# Charger_Control_Board_rev7.net
KiCad netlist of a schematic drawn in EAGLE
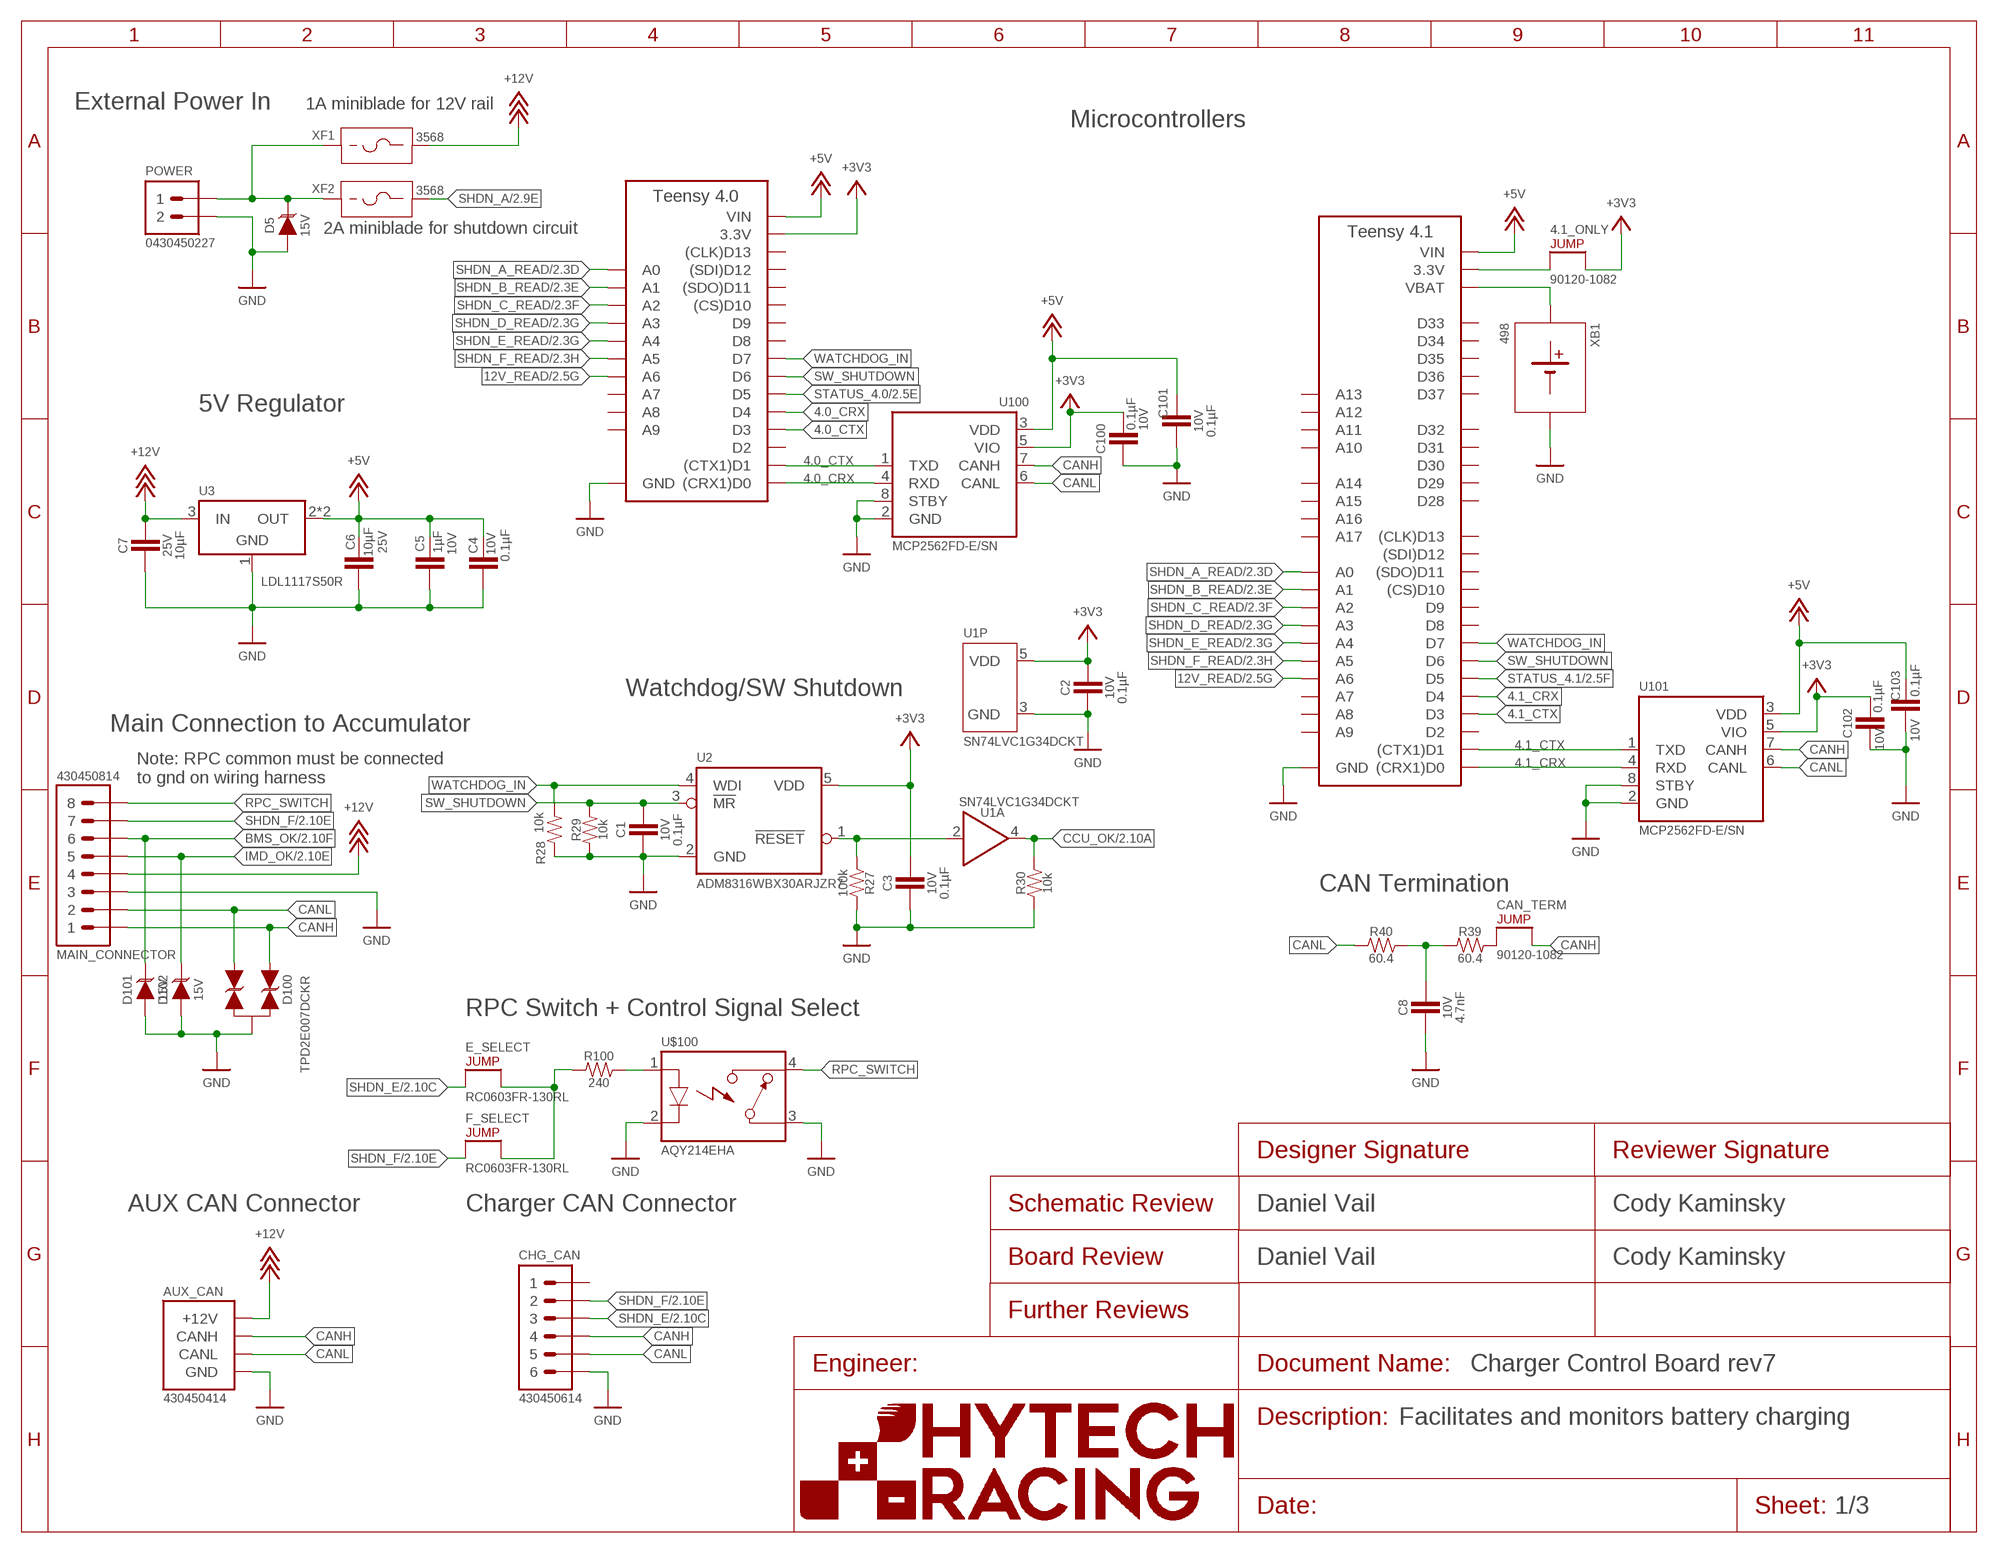
[diagram p0: schematic, sheet 1]
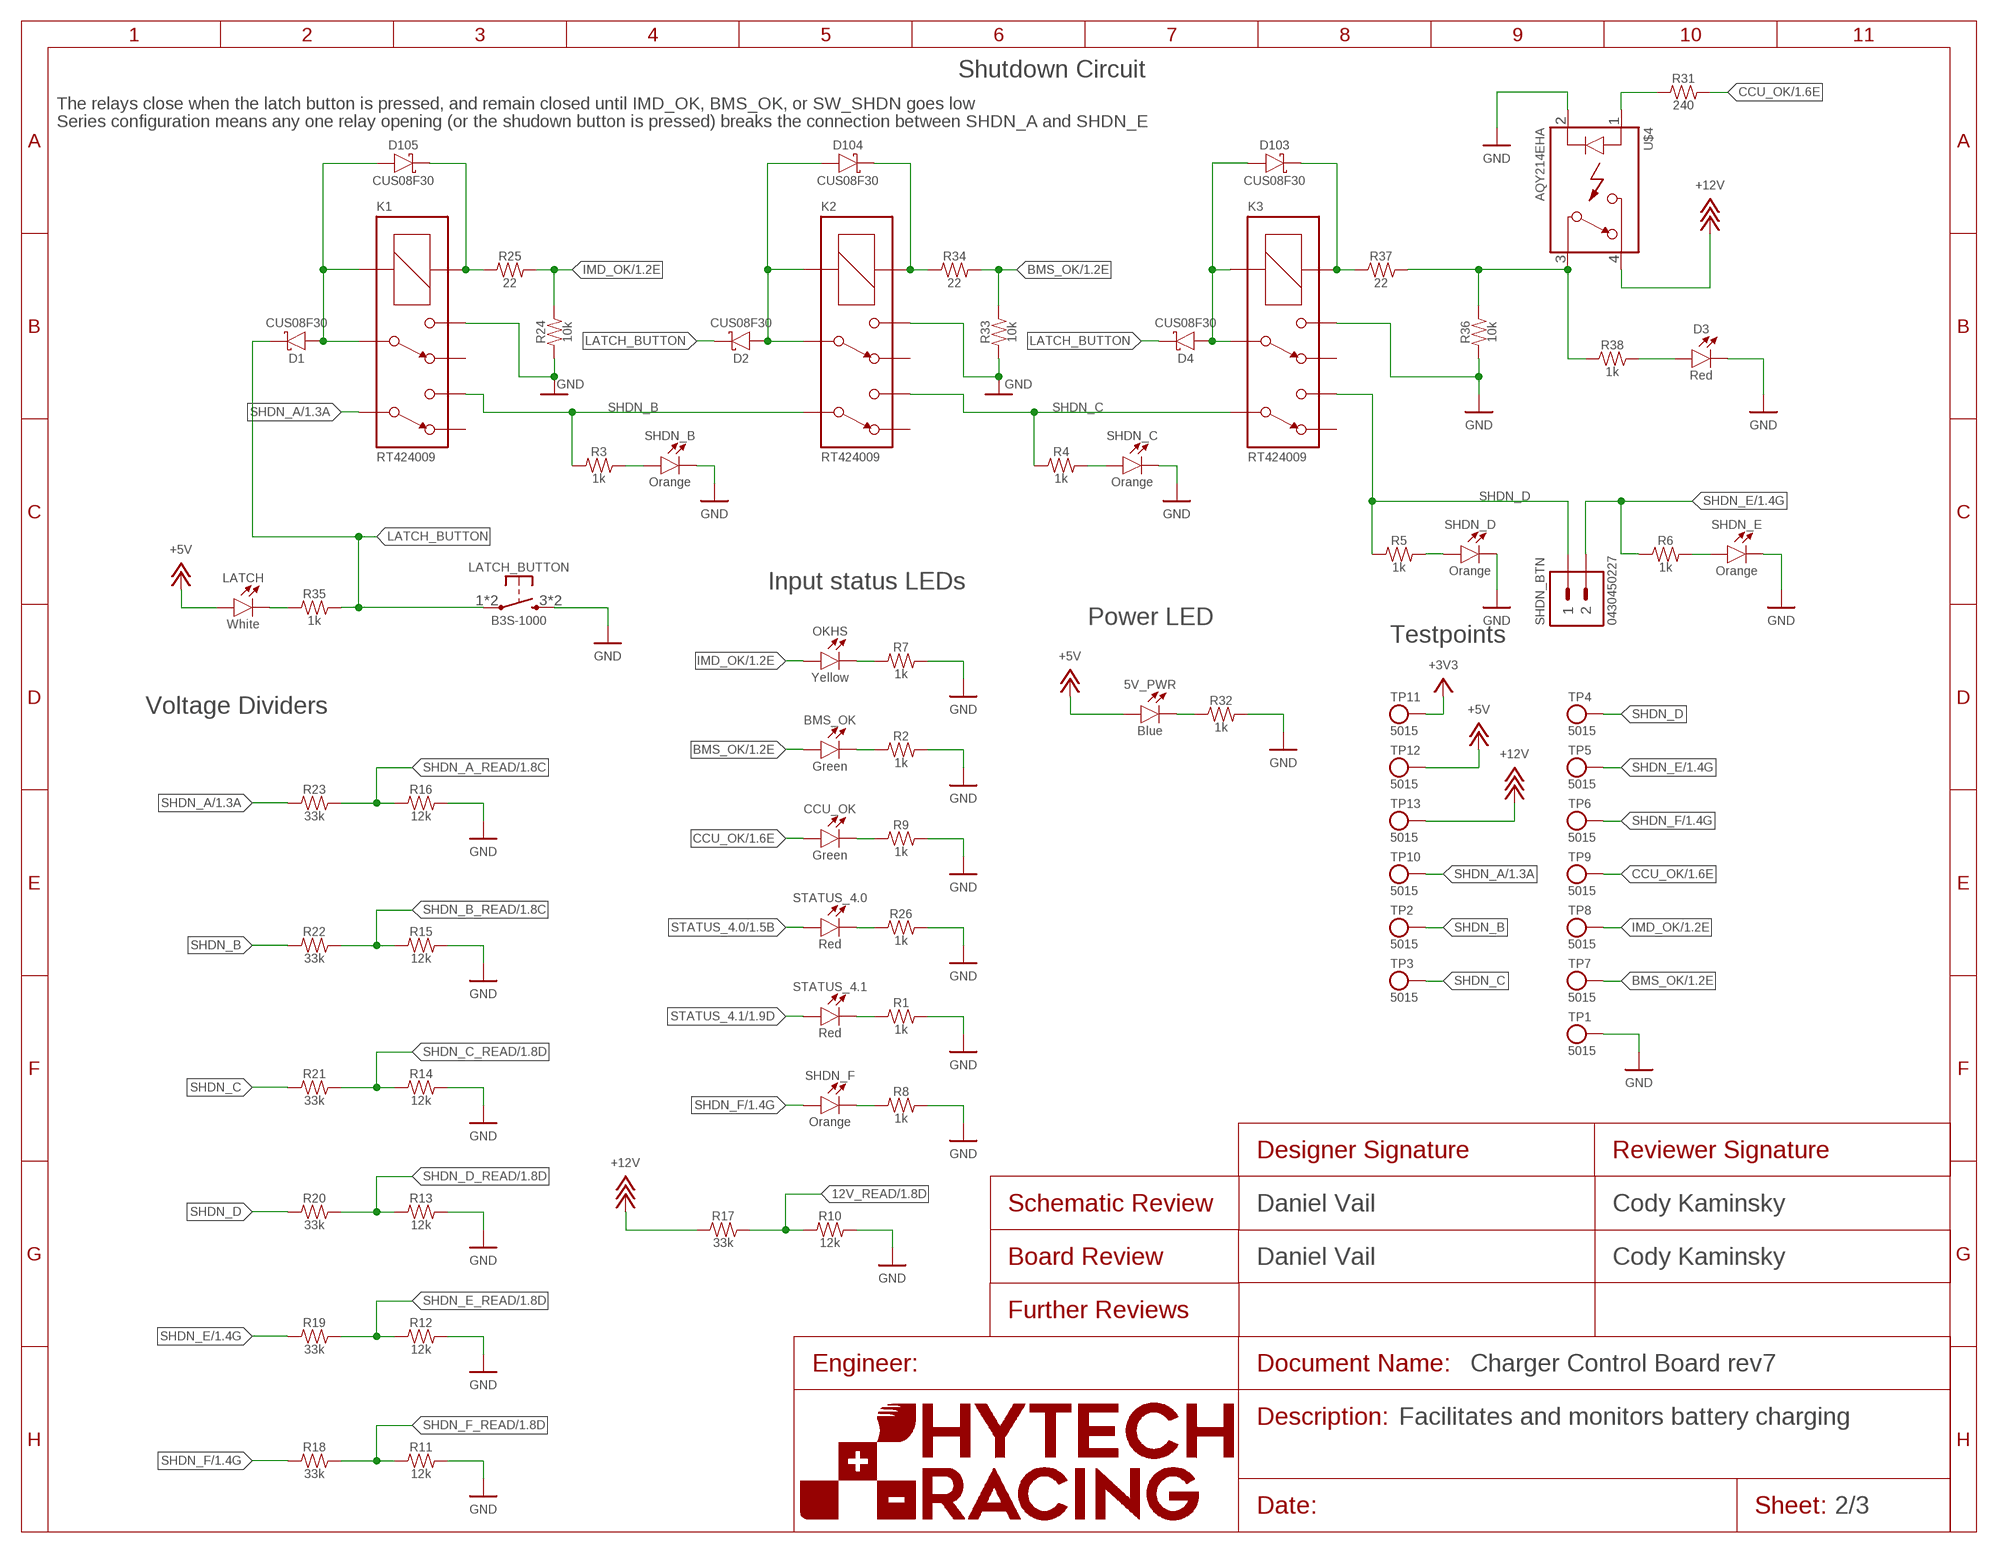
[diagram p1: schematic, sheet 2]
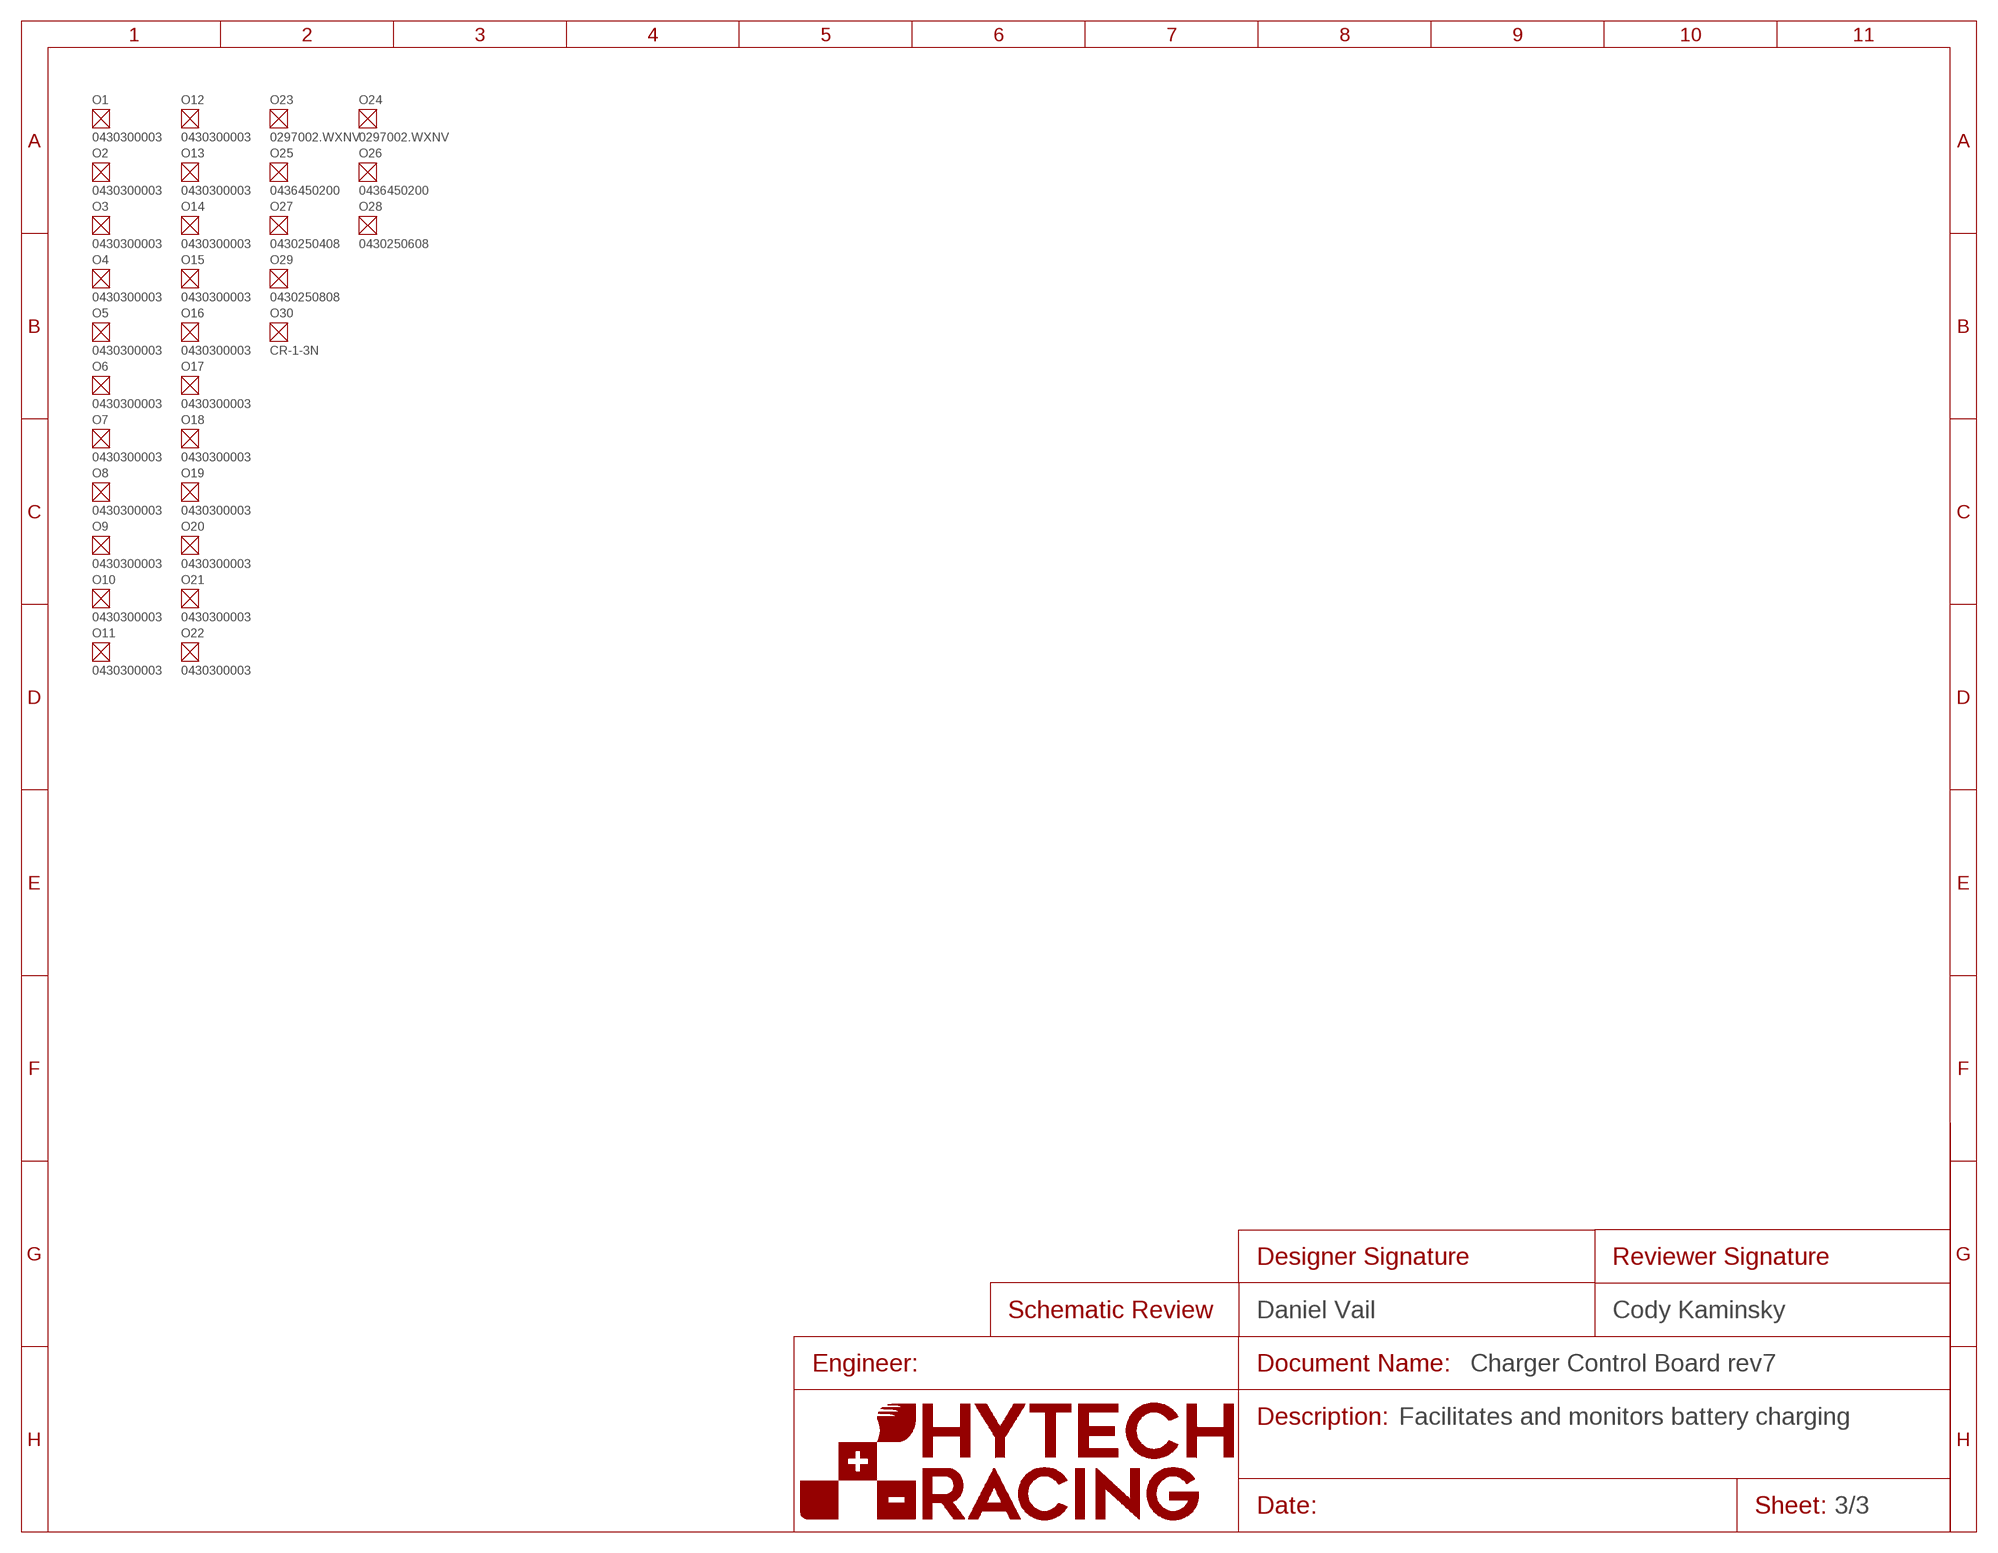
[diagram p2: schematic, sheet 3]

(export (version "E")
  (design (tool "Eeschema 10.0.6"))
  (components
    (comp (ref "4.1_ONLY")
      (value "JUMPER__1X02")
      (footprint "eagle-import:1X02")
      (fields (field (name "MANUFACTURER") "Molex") (field (name "MPN") "90120-1082 "))
      (libsource (lib "eagle-import") (part "JUMPER_?_1X02"))
    )
    (comp (ref "A1")
      (value "TEENSY_4.1")
      (footprint "eagle-import:TEENSY_LONG_EXT")
      (libsource (lib "eagle-import") (part "TEENSY_4.1"))
    )
    (comp (ref "A2")
      (value "TEENSY_4.0")
      (footprint "eagle-import:TEENSY_SHORT")
      (libsource (lib "eagle-import") (part "TEENSY_4.0"))
    )
    (comp (ref "AUX_CAN")
      (value "CONNECTOR-CAN_MF_T_V_")
      (footprint "eagle-import:MOLEX_MICROFIT_PTH_VERTICAL_04_DUAL")
      (fields (field (name "MPN") "430450414") (field (name "MANUFACTURER") "Molex"))
      (libsource (lib "eagle-import") (part "CONNECTOR-CAN_?_MF_T_V"))
    )
    (comp (ref "C1")
      (value "CAPACITOR_0603_10V_0.1UF")
      (footprint "eagle-import:0603-CAP")
      (fields
        (field (name "CAPACITANCE") "0.1µF")
        (field (name "MANUFACTURER") "Vishay Vitramon")
        (field (name "MPN") "VJ0603Y104JXQPW1BC")
        (field (name "TOLERANCE") "5%")
        (field (name "VOLTAGE") "10V")
      )
      (libsource (lib "eagle-import") (part "CAPACITOR_?_060310V_0.1UF"))
    )
    (comp (ref "C2")
      (value "CAPACITOR_0603_10V_0.1UF")
      (footprint "eagle-import:0603-CAP")
      (fields
        (field (name "CAPACITANCE") "0.1µF")
        (field (name "MANUFACTURER") "Vishay Vitramon")
        (field (name "MPN") "VJ0603Y104JXQPW1BC")
        (field (name "TOLERANCE") "5%")
        (field (name "VOLTAGE") "10V")
      )
      (libsource (lib "eagle-import") (part "CAPACITOR_?_060310V_0.1UF"))
    )
    (comp (ref "C3")
      (value "CAPACITOR_0603_10V_0.1UF")
      (footprint "eagle-import:0603-CAP")
      (fields
        (field (name "CAPACITANCE") "0.1µF")
        (field (name "MANUFACTURER") "Vishay Vitramon")
        (field (name "MPN") "VJ0603Y104JXQPW1BC")
        (field (name "TOLERANCE") "5%")
        (field (name "VOLTAGE") "10V")
      )
      (libsource (lib "eagle-import") (part "CAPACITOR_?_060310V_0.1UF"))
    )
    (comp (ref "C4")
      (value "CAPACITOR_0603_10V_0.1UF")
      (footprint "eagle-import:0603-CAP")
      (fields
        (field (name "CAPACITANCE") "0.1µF")
        (field (name "MANUFACTURER") "Vishay Vitramon")
        (field (name "MPN") "VJ0603Y104JXQPW1BC")
        (field (name "TOLERANCE") "5%")
        (field (name "VOLTAGE") "10V")
      )
      (libsource (lib "eagle-import") (part "CAPACITOR_?_060310V_0.1UF"))
    )
    (comp (ref "C5")
      (value "CAPACITOR_0603_10V_1UF")
      (footprint "eagle-import:0603-CAP")
      (fields
        (field (name "CAPACITANCE") "1µF")
        (field (name "MANUFACTURER") "Yageo")
        (field (name "MPN") "CC0603KRX7R6BB105")
        (field (name "TOLERANCE") "10%")
        (field (name "VOLTAGE") "10V")
      )
      (libsource (lib "eagle-import") (part "CAPACITOR_?_060310V_1UF"))
    )
    (comp (ref "C6")
      (value "CAPACITOR_0603_25V_10UF")
      (footprint "eagle-import:0603-CAP")
      (fields
        (field (name "CAPACITANCE") "10µF")
        (field (name "MANUFACTURER") "Murata Electronics")
        (field (name "MPN") "GRM188R61E106MA73D")
        (field (name "TOLERANCE") "20%")
        (field (name "VOLTAGE") "25V")
      )
      (libsource (lib "eagle-import") (part "CAPACITOR_?_060325V_10UF"))
    )
    (comp (ref "C7")
      (value "CAPACITOR_0603_25V_10UF")
      (footprint "eagle-import:0603-CAP")
      (fields
        (field (name "CAPACITANCE") "10µF")
        (field (name "MANUFACTURER") "Murata Electronics")
        (field (name "MPN") "GRM188R61E106MA73D")
        (field (name "TOLERANCE") "20%")
        (field (name "VOLTAGE") "25V")
      )
      (libsource (lib "eagle-import") (part "CAPACITOR_?_060325V_10UF"))
    )
    (comp (ref "C8")
      (value "CAPACITOR_0603_10V_4.7NF")
      (footprint "eagle-import:0603-CAP")
      (fields
        (field (name "CAPACITANCE") "4.7nF")
        (field (name "MANUFACTURER") "Würth Elektronik")
        (field (name "MPN") "885012206012")
        (field (name "TOLERANCE") "10%")
        (field (name "VOLTAGE") "10V")
      )
      (libsource (lib "eagle-import") (part "CAPACITOR_?_060310V_4.7NF"))
    )
    (comp (ref "C100")
      (value "CAPACITOR_0603_10V_0.1UF")
      (footprint "eagle-import:0603-CAP")
      (fields
        (field (name "CAPACITANCE") "0.1µF")
        (field (name "MANUFACTURER") "Vishay Vitramon")
        (field (name "MPN") "VJ0603Y104JXQPW1BC")
        (field (name "TOLERANCE") "5%")
        (field (name "VOLTAGE") "10V")
      )
      (libsource (lib "eagle-import") (part "CAPACITOR_?_060310V_0.1UF"))
    )
    (comp (ref "C101")
      (value "CAPACITOR_0603_10V_0.1UF")
      (footprint "eagle-import:0603-CAP")
      (fields
        (field (name "CAPACITANCE") "0.1µF")
        (field (name "MANUFACTURER") "Vishay Vitramon")
        (field (name "MPN") "VJ0603Y104JXQPW1BC")
        (field (name "TOLERANCE") "5%")
        (field (name "VOLTAGE") "10V")
      )
      (libsource (lib "eagle-import") (part "CAPACITOR_?_060310V_0.1UF"))
    )
    (comp (ref "C102")
      (value "CAPACITOR_0603_10V_0.1UF")
      (footprint "eagle-import:0603-CAP")
      (fields
        (field (name "CAPACITANCE") "0.1µF")
        (field (name "MANUFACTURER") "Vishay Vitramon")
        (field (name "MPN") "VJ0603Y104JXQPW1BC")
        (field (name "TOLERANCE") "5%")
        (field (name "VOLTAGE") "10V")
      )
      (libsource (lib "eagle-import") (part "CAPACITOR_?_060310V_0.1UF"))
    )
    (comp (ref "C103")
      (value "CAPACITOR_0603_10V_0.1UF")
      (footprint "eagle-import:0603-CAP")
      (fields
        (field (name "CAPACITANCE") "0.1µF")
        (field (name "MANUFACTURER") "Vishay Vitramon")
        (field (name "MPN") "VJ0603Y104JXQPW1BC")
        (field (name "TOLERANCE") "5%")
        (field (name "VOLTAGE") "10V")
      )
      (libsource (lib "eagle-import") (part "CAPACITOR_?_060310V_0.1UF"))
    )
    (comp (ref "CAN_TERM")
      (value "JUMPER__1X02")
      (footprint "eagle-import:1X02")
      (fields (field (name "MANUFACTURER") "Molex") (field (name "MPN") "90120-1082 "))
      (libsource (lib "eagle-import") (part "JUMPER_?_1X02"))
    )
    (comp (ref "CHG_CAN")
      (value "CONNECTOR-6_MF_T_V_")
      (footprint "eagle-import:MOLEX_MICROFIT_PTH_VERTICAL_06_DUAL")
      (fields (field (name "MPN") "430450614") (field (name "MANUFACTURER") "MOLEX"))
      (libsource (lib "eagle-import") (part "CONNECTOR-6_?_MF_T_V"))
    )
    (comp (ref "D5")
      (value "TVS_15V")
      (footprint "eagle-import:SOT-23")
      (fields
        (field (name "MANUFACTURER") "Vishay General Semiconductor - Diodes Division")
        (field (name "MPN") "GSOT15-E3-08")
        (field (name "VOLTAGE") "15V")
      )
      (libsource (lib "eagle-import") (part "TVS_15V"))
    )
    (comp (ref "D100")
      (value "TVS_BIDIRECTIONAL_DUAL")
      (footprint "eagle-import:SC-70-3")
      (fields (field (name "MPN") "TPD2E007DCKR") (field (name "MANUFACTURER") "Texas Instruments"))
      (libsource (lib "eagle-import") (part "TVS_BIDIRECTIONAL_DUAL"))
    )
    (comp (ref "D101")
      (value "TVS_15V")
      (footprint "eagle-import:SOT-23")
      (fields
        (field (name "MANUFACTURER") "Vishay General Semiconductor - Diodes Division")
        (field (name "MPN") "GSOT15-E3-08")
        (field (name "VOLTAGE") "15V")
      )
      (libsource (lib "eagle-import") (part "TVS_15V"))
    )
    (comp (ref "D102")
      (value "TVS_15V")
      (footprint "eagle-import:SOT-23")
      (fields
        (field (name "MANUFACTURER") "Vishay General Semiconductor - Diodes Division")
        (field (name "MPN") "GSOT15-E3-08")
        (field (name "VOLTAGE") "15V")
      )
      (libsource (lib "eagle-import") (part "TVS_15V"))
    )
    (comp (ref "E_SELECT")
      (value "JUMPER_0603_")
      (footprint "eagle-import:0603-RES")
      (fields (field (name "MPN") "RC0603FR-130RL") (field (name "MANUFACTURER") "YAGEO"))
      (libsource (lib "eagle-import") (part "JUMPER_?_0603"))
    )
    (comp (ref "F_SELECT")
      (value "JUMPER_0603_")
      (footprint "eagle-import:0603-RES")
      (fields (field (name "MPN") "RC0603FR-130RL") (field (name "MANUFACTURER") "YAGEO"))
      (libsource (lib "eagle-import") (part "JUMPER_?_0603"))
    )
    (comp (ref "MAIN_CONNECTOR")
      (value "CONNECTOR-8_MF_T_V_")
      (footprint "eagle-import:MOLEX_MICROFIT_PTH_VERTICAL_08_DUAL")
      (fields (field (name "MPN") "430450814") (field (name "MANUFACTURER") "MOLEX"))
      (libsource (lib "eagle-import") (part "CONNECTOR-8_?_MF_T_V"))
    )
    (comp (ref "POWER")
      (value "CONNECTOR-2_μF_T_V_")
      (footprint "eagle-import:MOLEX_MICROFIT_PTH_VERTICAL_02_DUAL")
      (fields (field (name "MPN") "0430450227") (field (name "MANUFACTURER") "Molex"))
      (libsource (lib "eagle-import") (part "CONNECTOR-2_?_μF_T_V"))
    )
    (comp (ref "R27")
      (value "RESISTOR_0603_100K")
      (footprint "eagle-import:0603-RES")
      (fields
        (field (name "MANUFACTURER") "Yageo")
        (field (name "MPN") "RC0603FR-07100KL")
        (field (name "POWER") "0.1W")
        (field (name "RESISTANCE") "100k")
      )
      (libsource (lib "eagle-import") (part "RESISTOR_?_0603100K"))
    )
    (comp (ref "R28")
      (value "RESISTOR_0603_10K")
      (footprint "eagle-import:0603-RES")
      (fields
        (field (name "MANUFACTURER") "Yageo")
        (field (name "MPN") "RC0603FR-0710KL")
        (field (name "POWER") "0.1W")
        (field (name "RESISTANCE") "10k")
      )
      (libsource (lib "eagle-import") (part "RESISTOR_?_060310K"))
    )
    (comp (ref "R29")
      (value "RESISTOR_0603_10K")
      (footprint "eagle-import:0603-RES")
      (fields
        (field (name "MANUFACTURER") "Yageo")
        (field (name "MPN") "RC0603FR-0710KL")
        (field (name "POWER") "0.1W")
        (field (name "RESISTANCE") "10k")
      )
      (libsource (lib "eagle-import") (part "RESISTOR_?_060310K"))
    )
    (comp (ref "R30")
      (value "RESISTOR_0603_10K")
      (footprint "eagle-import:0603-RES")
      (fields
        (field (name "MANUFACTURER") "Yageo")
        (field (name "MPN") "RC0603FR-0710KL")
        (field (name "POWER") "0.1W")
        (field (name "RESISTANCE") "10k")
      )
      (libsource (lib "eagle-import") (part "RESISTOR_?_060310K"))
    )
    (comp (ref "R39")
      (value "RESISTOR_0603_60.4")
      (footprint "eagle-import:0603-RES")
      (fields
        (field (name "MANUFACTURER") "Yageo")
        (field (name "MPN") "RC0603FR-0760R4L")
        (field (name "POWER") "0.1W")
        (field (name "RESISTANCE") "60.4")
      )
      (libsource (lib "eagle-import") (part "RESISTOR_?_060360.4"))
    )
    (comp (ref "R40")
      (value "RESISTOR_0603_60.4")
      (footprint "eagle-import:0603-RES")
      (fields
        (field (name "MANUFACTURER") "Yageo")
        (field (name "MPN") "RC0603FR-0760R4L")
        (field (name "POWER") "0.1W")
        (field (name "RESISTANCE") "60.4")
      )
      (libsource (lib "eagle-import") (part "RESISTOR_?_060360.4"))
    )
    (comp (ref "R100")
      (value "RESISTOR_0603_240")
      (footprint "eagle-import:0603-RES")
      (fields
        (field (name "MANUFACTURER") "Yageo")
        (field (name "MPN") "RC0603FR-07240RL")
        (field (name "POWER") "0.1W")
        (field (name "RESISTANCE") "240")
      )
      (libsource (lib "eagle-import") (part "HyTechDevices_Jumper_RESISTOR_?_0603240"))
    )
    (comp (ref "U$100")
      (value "RELAY_SOLIDSTATE_NO")
      (footprint "eagle-import:DIP-4")
      (fields (field (name "MPN") "AQY214EHA") (field (name "MANUFACTURER") "AQY214EHA"))
      (libsource (lib "eagle-import") (part "RELAY_SOLIDSTATE_NO"))
    )
    (comp (ref "U1")
      (value "LOGICGATE_BUFFER")
      (footprint "eagle-import:SC-70-5")
      (fields (field (name "MANUFACTURER") "Texas Instruments"))
      (libsource (lib "eagle-import") (part "LOGICGATE_BUFFER"))
    )
    (comp (ref "U2")
      (value "ADM8316WBX30")
      (footprint "eagle-import:SOT-23-5")
      (fields (field (name "MANUFACTURER") "Analog Devices Inc.") (field (name "MPN") "ADM8316WBX30ARJZR7"))
      (libsource (lib "eagle-import") (part "ADM8316WBX30"))
    )
    (comp (ref "U3")
      (value "VOLTAGE_REGULATOR_SOT-223_5V")
      (footprint "eagle-import:SOT-223")
      (fields (field (name "MANUFACTURER") "STMicroelectronics") (field (name "MPN") "LDL1117S50R"))
      (libsource (lib "eagle-import") (part "VOLTAGE_REGULATOR_?_SOT-2235V"))
    )
    (comp (ref "U100")
      (value "MCP2562FD")
      (footprint "eagle-import:SOIC-08(NARROW,0.15_)")
      (fields (field (name "MPN") "MCP2562FD-E/SN") (field (name "MANUFACTURER") "Microchip Technology"))
      (libsource (lib "eagle-import") (part "MCP2562FD"))
    )
    (comp (ref "U101")
      (value "MCP2562FD")
      (footprint "eagle-import:SOIC-08(NARROW,0.15_)")
      (fields (field (name "MPN") "MCP2562FD-E/SN") (field (name "MANUFACTURER") "Microchip Technology"))
      (libsource (lib "eagle-import") (part "MCP2562FD"))
    )
    (comp (ref "XB1")
      (value "BATTERY_HOLDER_KEYSTONE_498")
      (footprint "eagle-import:498")
      (fields (field (name "MPN") "498") (field (name "MANUFACTURER") "Keystone Electronics"))
      (libsource (lib "eagle-import") (part "BATTERY_HOLDER_KEYSTONE_498"))
    )
    (comp (ref "XF1")
      (value "FUSE_HOLDER_MINIBLADEPTH")
      (footprint "eagle-import:3568")
      (fields (field (name "MANUFACTURER") "Keystone") (field (name "MPN") "3568"))
      (libsource (lib "eagle-import") (part "FUSE_HOLDER_PTHMINIBLADE"))
    )
    (comp (ref "XF2")
      (value "FUSE_HOLDER_MINIBLADEPTH")
      (footprint "eagle-import:3568")
      (fields (field (name "MANUFACTURER") "Keystone") (field (name "MPN") "3568"))
      (libsource (lib "eagle-import") (part "FUSE_HOLDER_PTHMINIBLADE"))
    )
    (comp (ref "5V_PWR")
      (value "LED_0603_BLUE")
      (footprint "eagle-import:0603-LED")
      (fields
        (field (name "COLOR") "Blue")
        (field (name "MANUFACTURER") "Kingbright")
        (field (name "MPN") "APT1608VBC/D")
      )
      (libsource (lib "eagle-import") (part "LED_?_0603BLUE"))
    )
    (comp (ref "BMS_OK")
      (value "LED_0603_GREEN")
      (footprint "eagle-import:0603-LED")
      (fields
        (field (name "COLOR") "Green")
        (field (name "MANUFACTURER") "Kingbright")
        (field (name "MPN") "APT1608ZGCK")
      )
      (libsource (lib "eagle-import") (part "LED_?_0603GREEN"))
    )
    (comp (ref "CCU_OK")
      (value "LED_0603_GREEN")
      (footprint "eagle-import:0603-LED")
      (fields
        (field (name "COLOR") "Green")
        (field (name "MANUFACTURER") "Kingbright")
        (field (name "MPN") "APT1608ZGCK")
      )
      (libsource (lib "eagle-import") (part "LED_?_0603GREEN"))
    )
    (comp (ref "D1")
      (value "SCHOTTKY_SOD323_30V")
      (footprint "eagle-import:SOD-323")
      (fields
        (field (name "MANUFACTURER") "Toshiba Semiconductor and Storage")
        (field (name "MPN") "CUS08F30")
        (field (name "VOLTAGE") "30V")
      )
      (libsource (lib "eagle-import") (part "SCHOTTKY_?_SOD32330V"))
    )
    (comp (ref "D2")
      (value "SCHOTTKY_SOD323_30V")
      (footprint "eagle-import:SOD-323")
      (fields
        (field (name "MANUFACTURER") "Toshiba Semiconductor and Storage")
        (field (name "MPN") "CUS08F30")
        (field (name "VOLTAGE") "30V")
      )
      (libsource (lib "eagle-import") (part "SCHOTTKY_?_SOD32330V"))
    )
    (comp (ref "D3")
      (value "LED_0603_RED")
      (footprint "eagle-import:0603-LED")
      (fields
        (field (name "COLOR") "Red")
        (field (name "MANUFACTURER") "Kingbright")
        (field (name "MPN") "APT1608SECK/J3-PRV")
      )
      (libsource (lib "eagle-import") (part "LED_?_0603RED"))
    )
    (comp (ref "D4")
      (value "SCHOTTKY_SOD323_30V")
      (footprint "eagle-import:SOD-323")
      (fields
        (field (name "MANUFACTURER") "Toshiba Semiconductor and Storage")
        (field (name "MPN") "CUS08F30")
        (field (name "VOLTAGE") "30V")
      )
      (libsource (lib "eagle-import") (part "SCHOTTKY_?_SOD32330V"))
    )
    (comp (ref "D103")
      (value "SCHOTTKY_SOD323_30V")
      (footprint "eagle-import:SOD-323")
      (fields
        (field (name "MANUFACTURER") "Toshiba Semiconductor and Storage")
        (field (name "MPN") "CUS08F30")
        (field (name "VOLTAGE") "30V")
      )
      (libsource (lib "eagle-import") (part "SCHOTTKY_?_SOD32330V"))
    )
    (comp (ref "D104")
      (value "SCHOTTKY_SOD323_30V")
      (footprint "eagle-import:SOD-323")
      (fields
        (field (name "MANUFACTURER") "Toshiba Semiconductor and Storage")
        (field (name "MPN") "CUS08F30")
        (field (name "VOLTAGE") "30V")
      )
      (libsource (lib "eagle-import") (part "SCHOTTKY_?_SOD32330V"))
    )
    (comp (ref "D105")
      (value "SCHOTTKY_SOD323_30V")
      (footprint "eagle-import:SOD-323")
      (fields
        (field (name "MANUFACTURER") "Toshiba Semiconductor and Storage")
        (field (name "MPN") "CUS08F30")
        (field (name "VOLTAGE") "30V")
      )
      (libsource (lib "eagle-import") (part "SCHOTTKY_?_SOD32330V"))
    )
    (comp (ref "K1")
      (value "RELAY_DPDT")
      (footprint "eagle-import:RT_2_")
      (fields (field (name "MPN") "RT424009") (field (name "MANUFACTURER") "TE Connectivity"))
      (libsource (lib "eagle-import") (part "RELAY_DPDT"))
    )
    (comp (ref "K2")
      (value "RELAY_DPDT")
      (footprint "eagle-import:RT_2_")
      (fields (field (name "MPN") "RT424009") (field (name "MANUFACTURER") "TE Connectivity"))
      (libsource (lib "eagle-import") (part "RELAY_DPDT"))
    )
    (comp (ref "K3")
      (value "RELAY_DPDT")
      (footprint "eagle-import:RT_2_")
      (fields (field (name "MPN") "RT424009") (field (name "MANUFACTURER") "TE Connectivity"))
      (libsource (lib "eagle-import") (part "RELAY_DPDT"))
    )
    (comp (ref "LATCH")
      (value "LED_0603_WHITE")
      (footprint "eagle-import:0603-LED")
      (fields
        (field (name "COLOR") "White")
        (field (name "MANUFACTURER") "Bivar Inc.")
        (field (name "MPN") "SM0603UWC")
      )
      (libsource (lib "eagle-import") (part "LED_?_0603WHITE"))
    )
    (comp (ref "LATCH_BUTTON")
      (value "BUTTON")
      (footprint "eagle-import:B3S-100X")
      (fields (field (name "MPN") "B3S-1000") (field (name "MANUFACTURER") "Omron"))
      (libsource (lib "eagle-import") (part "BUTTON"))
    )
    (comp (ref "OKHS")
      (value "LED_0603_YELLOW")
      (footprint "eagle-import:0603-LED")
      (fields
        (field (name "COLOR") "Yellow")
        (field (name "MANUFACTURER") "Kingbright")
        (field (name "MPN") "APT1608SYCK/J3-PRV")
      )
      (libsource (lib "eagle-import") (part "LED_?_0603YELLOW"))
    )
    (comp (ref "R1")
      (value "RESISTOR_0603_1K")
      (footprint "eagle-import:0603-RES")
      (fields
        (field (name "MANUFACTURER") "Yageo")
        (field (name "MPN") "RC0603FR-071KL")
        (field (name "POWER") "0.1W")
        (field (name "RESISTANCE") "1k")
      )
      (libsource (lib "eagle-import") (part "RESISTOR_?_06031K"))
    )
    (comp (ref "R2")
      (value "RESISTOR_0603_1K")
      (footprint "eagle-import:0603-RES")
      (fields
        (field (name "MANUFACTURER") "Yageo")
        (field (name "MPN") "RC0603FR-071KL")
        (field (name "POWER") "0.1W")
        (field (name "RESISTANCE") "1k")
      )
      (libsource (lib "eagle-import") (part "RESISTOR_?_06031K"))
    )
    (comp (ref "R3")
      (value "RESISTOR_0603_1K")
      (footprint "eagle-import:0603-RES")
      (fields
        (field (name "MANUFACTURER") "Yageo")
        (field (name "MPN") "RC0603FR-071KL")
        (field (name "POWER") "0.1W")
        (field (name "RESISTANCE") "1k")
      )
      (libsource (lib "eagle-import") (part "RESISTOR_?_06031K"))
    )
    (comp (ref "R4")
      (value "RESISTOR_0603_1K")
      (footprint "eagle-import:0603-RES")
      (fields
        (field (name "MANUFACTURER") "Yageo")
        (field (name "MPN") "RC0603FR-071KL")
        (field (name "POWER") "0.1W")
        (field (name "RESISTANCE") "1k")
      )
      (libsource (lib "eagle-import") (part "RESISTOR_?_06031K"))
    )
    (comp (ref "R5")
      (value "RESISTOR_0603_1K")
      (footprint "eagle-import:0603-RES")
      (fields
        (field (name "MANUFACTURER") "Yageo")
        (field (name "MPN") "RC0603FR-071KL")
        (field (name "POWER") "0.1W")
        (field (name "RESISTANCE") "1k")
      )
      (libsource (lib "eagle-import") (part "RESISTOR_?_06031K"))
    )
    (comp (ref "R6")
      (value "RESISTOR_0603_1K")
      (footprint "eagle-import:0603-RES")
      (fields
        (field (name "MANUFACTURER") "Yageo")
        (field (name "MPN") "RC0603FR-071KL")
        (field (name "POWER") "0.1W")
        (field (name "RESISTANCE") "1k")
      )
      (libsource (lib "eagle-import") (part "RESISTOR_?_06031K"))
    )
    (comp (ref "R7")
      (value "RESISTOR_0603_1K")
      (footprint "eagle-import:0603-RES")
      (fields
        (field (name "MANUFACTURER") "Yageo")
        (field (name "MPN") "RC0603FR-071KL")
        (field (name "POWER") "0.1W")
        (field (name "RESISTANCE") "1k")
      )
      (libsource (lib "eagle-import") (part "RESISTOR_?_06031K"))
    )
    (comp (ref "R8")
      (value "RESISTOR_0603_1K")
      (footprint "eagle-import:0603-RES")
      (fields
        (field (name "MANUFACTURER") "Yageo")
        (field (name "MPN") "RC0603FR-071KL")
        (field (name "POWER") "0.1W")
        (field (name "RESISTANCE") "1k")
      )
      (libsource (lib "eagle-import") (part "RESISTOR_?_06031K"))
    )
    (comp (ref "R9")
      (value "RESISTOR_0603_1K")
      (footprint "eagle-import:0603-RES")
      (fields
        (field (name "MANUFACTURER") "Yageo")
        (field (name "MPN") "RC0603FR-071KL")
        (field (name "POWER") "0.1W")
        (field (name "RESISTANCE") "1k")
      )
      (libsource (lib "eagle-import") (part "RESISTOR_?_06031K"))
    )
    (comp (ref "R10")
      (value "RESISTOR_0603_12K")
      (footprint "eagle-import:0603-RES")
      (fields
        (field (name "MANUFACTURER") "Yageo")
        (field (name "MPN") "RC0603FR-0712KL")
        (field (name "POWER") "0.1W")
        (field (name "RESISTANCE") "12k")
      )
      (libsource (lib "eagle-import") (part "RESISTOR_?_060312K"))
    )
    (comp (ref "R11")
      (value "RESISTOR_0603_12K")
      (footprint "eagle-import:0603-RES")
      (fields
        (field (name "MANUFACTURER") "Yageo")
        (field (name "MPN") "RC0603FR-0712KL")
        (field (name "POWER") "0.1W")
        (field (name "RESISTANCE") "12k")
      )
      (libsource (lib "eagle-import") (part "RESISTOR_?_060312K"))
    )
    (comp (ref "R12")
      (value "RESISTOR_0603_12K")
      (footprint "eagle-import:0603-RES")
      (fields
        (field (name "MANUFACTURER") "Yageo")
        (field (name "MPN") "RC0603FR-0712KL")
        (field (name "POWER") "0.1W")
        (field (name "RESISTANCE") "12k")
      )
      (libsource (lib "eagle-import") (part "RESISTOR_?_060312K"))
    )
    (comp (ref "R13")
      (value "RESISTOR_0603_12K")
      (footprint "eagle-import:0603-RES")
      (fields
        (field (name "MANUFACTURER") "Yageo")
        (field (name "MPN") "RC0603FR-0712KL")
        (field (name "POWER") "0.1W")
        (field (name "RESISTANCE") "12k")
      )
      (libsource (lib "eagle-import") (part "RESISTOR_?_060312K"))
    )
    (comp (ref "R14")
      (value "RESISTOR_0603_12K")
      (footprint "eagle-import:0603-RES")
      (fields
        (field (name "MANUFACTURER") "Yageo")
        (field (name "MPN") "RC0603FR-0712KL")
        (field (name "POWER") "0.1W")
        (field (name "RESISTANCE") "12k")
      )
      (libsource (lib "eagle-import") (part "RESISTOR_?_060312K"))
    )
    (comp (ref "R15")
      (value "RESISTOR_0603_12K")
      (footprint "eagle-import:0603-RES")
      (fields
        (field (name "MANUFACTURER") "Yageo")
        (field (name "MPN") "RC0603FR-0712KL")
        (field (name "POWER") "0.1W")
        (field (name "RESISTANCE") "12k")
      )
      (libsource (lib "eagle-import") (part "RESISTOR_?_060312K"))
    )
    (comp (ref "R16")
      (value "RESISTOR_0603_12K")
      (footprint "eagle-import:0603-RES")
      (fields
        (field (name "MANUFACTURER") "Yageo")
        (field (name "MPN") "RC0603FR-0712KL")
        (field (name "POWER") "0.1W")
        (field (name "RESISTANCE") "12k")
      )
      (libsource (lib "eagle-import") (part "RESISTOR_?_060312K"))
    )
    (comp (ref "R17")
      (value "RESISTOR_0603_33K")
      (footprint "eagle-import:0603-RES")
      (fields
        (field (name "MANUFACTURER") "Rohm Semiconductor")
        (field (name "MPN") "KTR03EZPF3302")
        (field (name "POWER") "0.1W")
        (field (name "RESISTANCE") "33k")
      )
      (libsource (lib "eagle-import") (part "RESISTOR_?_060333K"))
    )
    (comp (ref "R18")
      (value "RESISTOR_0603_33K")
      (footprint "eagle-import:0603-RES")
      (fields
        (field (name "MANUFACTURER") "Rohm Semiconductor")
        (field (name "MPN") "KTR03EZPF3302")
        (field (name "POWER") "0.1W")
        (field (name "RESISTANCE") "33k")
      )
      (libsource (lib "eagle-import") (part "RESISTOR_?_060333K"))
    )
    (comp (ref "R19")
      (value "RESISTOR_0603_33K")
      (footprint "eagle-import:0603-RES")
      (fields
        (field (name "MANUFACTURER") "Rohm Semiconductor")
        (field (name "MPN") "KTR03EZPF3302")
        (field (name "POWER") "0.1W")
        (field (name "RESISTANCE") "33k")
      )
      (libsource (lib "eagle-import") (part "RESISTOR_?_060333K"))
    )
    (comp (ref "R20")
      (value "RESISTOR_0603_33K")
      (footprint "eagle-import:0603-RES")
      (fields
        (field (name "MANUFACTURER") "Rohm Semiconductor")
        (field (name "MPN") "KTR03EZPF3302")
        (field (name "POWER") "0.1W")
        (field (name "RESISTANCE") "33k")
      )
      (libsource (lib "eagle-import") (part "RESISTOR_?_060333K"))
    )
    (comp (ref "R21")
      (value "RESISTOR_0603_33K")
      (footprint "eagle-import:0603-RES")
      (fields
        (field (name "MANUFACTURER") "Rohm Semiconductor")
        (field (name "MPN") "KTR03EZPF3302")
        (field (name "POWER") "0.1W")
        (field (name "RESISTANCE") "33k")
      )
      (libsource (lib "eagle-import") (part "RESISTOR_?_060333K"))
    )
    (comp (ref "R22")
      (value "RESISTOR_0603_33K")
      (footprint "eagle-import:0603-RES")
      (fields
        (field (name "MANUFACTURER") "Rohm Semiconductor")
        (field (name "MPN") "KTR03EZPF3302")
        (field (name "POWER") "0.1W")
        (field (name "RESISTANCE") "33k")
      )
      (libsource (lib "eagle-import") (part "RESISTOR_?_060333K"))
    )
    (comp (ref "R23")
      (value "RESISTOR_0603_33K")
      (footprint "eagle-import:0603-RES")
      (fields
        (field (name "MANUFACTURER") "Rohm Semiconductor")
        (field (name "MPN") "KTR03EZPF3302")
        (field (name "POWER") "0.1W")
        (field (name "RESISTANCE") "33k")
      )
      (libsource (lib "eagle-import") (part "RESISTOR_?_060333K"))
    )
    (comp (ref "R24")
      (value "RESISTOR_0603_10K")
      (footprint "eagle-import:0603-RES")
      (fields
        (field (name "MANUFACTURER") "Yageo")
        (field (name "MPN") "RC0603FR-0710KL")
        (field (name "POWER") "0.1W")
        (field (name "RESISTANCE") "10k")
      )
      (libsource (lib "eagle-import") (part "RESISTOR_?_060310K"))
    )
    (comp (ref "R25")
      (value "RESISTOR_0603_22")
      (footprint "eagle-import:0603-RES")
      (fields
        (field (name "MANUFACTURER") "Yageo")
        (field (name "MPN") "RC0603FR-0722RL")
        (field (name "POWER") "0.1W")
        (field (name "RESISTANCE") "22")
      )
      (libsource (lib "eagle-import") (part "RESISTOR_?_060322"))
    )
    (comp (ref "R26")
      (value "RESISTOR_0603_1K")
      (footprint "eagle-import:0603-RES")
      (fields
        (field (name "MANUFACTURER") "Yageo")
        (field (name "MPN") "RC0603FR-071KL")
        (field (name "POWER") "0.1W")
        (field (name "RESISTANCE") "1k")
      )
      (libsource (lib "eagle-import") (part "RESISTOR_?_06031K"))
    )
    (comp (ref "R31")
      (value "RESISTOR_0603_240")
      (footprint "eagle-import:0603-RES")
      (fields
        (field (name "MANUFACTURER") "Yageo")
        (field (name "MPN") "RC0603FR-07240RL")
        (field (name "POWER") "0.1W")
        (field (name "RESISTANCE") "240")
      )
      (libsource (lib "eagle-import") (part "RESISTOR_?_0603240"))
    )
    (comp (ref "R32")
      (value "RESISTOR_0603_1K")
      (footprint "eagle-import:0603-RES")
      (fields
        (field (name "MANUFACTURER") "Yageo")
        (field (name "MPN") "RC0603FR-071KL")
        (field (name "POWER") "0.1W")
        (field (name "RESISTANCE") "1k")
      )
      (libsource (lib "eagle-import") (part "RESISTOR_?_06031K"))
    )
    (comp (ref "R33")
      (value "RESISTOR_0603_10K")
      (footprint "eagle-import:0603-RES")
      (fields
        (field (name "MANUFACTURER") "Yageo")
        (field (name "MPN") "RC0603FR-0710KL")
        (field (name "POWER") "0.1W")
        (field (name "RESISTANCE") "10k")
      )
      (libsource (lib "eagle-import") (part "RESISTOR_?_060310K"))
    )
    (comp (ref "R34")
      (value "RESISTOR_0603_22")
      (footprint "eagle-import:0603-RES")
      (fields
        (field (name "MANUFACTURER") "Yageo")
        (field (name "MPN") "RC0603FR-0722RL")
        (field (name "POWER") "0.1W")
        (field (name "RESISTANCE") "22")
      )
      (libsource (lib "eagle-import") (part "RESISTOR_?_060322"))
    )
    (comp (ref "R35")
      (value "RESISTOR_0603_1K")
      (footprint "eagle-import:0603-RES")
      (fields
        (field (name "MANUFACTURER") "Yageo")
        (field (name "MPN") "RC0603FR-071KL")
        (field (name "POWER") "0.1W")
        (field (name "RESISTANCE") "1k")
      )
      (libsource (lib "eagle-import") (part "RESISTOR_?_06031K"))
    )
    (comp (ref "R36")
      (value "RESISTOR_0603_10K")
      (footprint "eagle-import:0603-RES")
      (fields
        (field (name "MANUFACTURER") "Yageo")
        (field (name "MPN") "RC0603FR-0710KL")
        (field (name "POWER") "0.1W")
        (field (name "RESISTANCE") "10k")
      )
      (libsource (lib "eagle-import") (part "RESISTOR_?_060310K"))
    )
    (comp (ref "R37")
      (value "RESISTOR_0603_22")
      (footprint "eagle-import:0603-RES")
      (fields
        (field (name "MANUFACTURER") "Yageo")
        (field (name "MPN") "RC0603FR-0722RL")
        (field (name "POWER") "0.1W")
        (field (name "RESISTANCE") "22")
      )
      (libsource (lib "eagle-import") (part "RESISTOR_?_060322"))
    )
    (comp (ref "R38")
      (value "RESISTOR_0603_1K")
      (footprint "eagle-import:0603-RES")
      (fields
        (field (name "MANUFACTURER") "Yageo")
        (field (name "MPN") "RC0603FR-071KL")
        (field (name "POWER") "0.1W")
        (field (name "RESISTANCE") "1k")
      )
      (libsource (lib "eagle-import") (part "RESISTOR_?_06031K"))
    )
    (comp (ref "SHDN_B")
      (value "LED_0603_ORANGE")
      (footprint "eagle-import:0603-LED")
      (fields
        (field (name "COLOR") "Orange")
        (field (name "MANUFACTURER") "Kingbright")
        (field (name "MPN") "APT1608SECK")
      )
      (libsource (lib "eagle-import") (part "LED_?_0603ORANGE"))
    )
    (comp (ref "SHDN_BTN")
      (value "CONNECTOR-2_μF_T_V_")
      (footprint "eagle-import:MOLEX_MICROFIT_PTH_VERTICAL_02_DUAL")
      (fields (field (name "MPN") "0430450227") (field (name "MANUFACTURER") "Molex"))
      (libsource (lib "eagle-import") (part "CONNECTOR-2_?_μF_T_V"))
    )
    (comp (ref "SHDN_C")
      (value "LED_0603_ORANGE")
      (footprint "eagle-import:0603-LED")
      (fields
        (field (name "COLOR") "Orange")
        (field (name "MANUFACTURER") "Kingbright")
        (field (name "MPN") "APT1608SECK")
      )
      (libsource (lib "eagle-import") (part "LED_?_0603ORANGE"))
    )
    (comp (ref "SHDN_D")
      (value "LED_0603_ORANGE")
      (footprint "eagle-import:0603-LED")
      (fields
        (field (name "COLOR") "Orange")
        (field (name "MANUFACTURER") "Kingbright")
        (field (name "MPN") "APT1608SECK")
      )
      (libsource (lib "eagle-import") (part "LED_?_0603ORANGE"))
    )
    (comp (ref "SHDN_E")
      (value "LED_0603_ORANGE")
      (footprint "eagle-import:0603-LED")
      (fields
        (field (name "COLOR") "Orange")
        (field (name "MANUFACTURER") "Kingbright")
        (field (name "MPN") "APT1608SECK")
      )
      (libsource (lib "eagle-import") (part "LED_?_0603ORANGE"))
    )
    (comp (ref "SHDN_F")
      (value "LED_0603_ORANGE")
      (footprint "eagle-import:0603-LED")
      (fields
        (field (name "COLOR") "Orange")
        (field (name "MANUFACTURER") "Kingbright")
        (field (name "MPN") "APT1608SECK")
      )
      (libsource (lib "eagle-import") (part "LED_?_0603ORANGE"))
    )
    (comp (ref "STATUS_4.0")
      (value "LED_0603_RED")
      (footprint "eagle-import:0603-LED")
      (fields
        (field (name "COLOR") "Red")
        (field (name "MANUFACTURER") "Kingbright")
        (field (name "MPN") "APT1608SECK/J3-PRV")
      )
      (libsource (lib "eagle-import") (part "LED_?_0603RED"))
    )
    (comp (ref "STATUS_4.1")
      (value "LED_0603_RED")
      (footprint "eagle-import:0603-LED")
      (fields
        (field (name "COLOR") "Red")
        (field (name "MANUFACTURER") "Kingbright")
        (field (name "MPN") "APT1608SECK/J3-PRV")
      )
      (libsource (lib "eagle-import") (part "LED_?_0603RED"))
    )
    (comp (ref "TP1")
      (value "TEST_POINT")
      (footprint "eagle-import:5015")
      (fields (field (name "MPN") "5015") (field (name "MANUFACTURER") "Keystone Electronics"))
      (libsource (lib "eagle-import") (part "TEST_POINT"))
    )
    (comp (ref "TP2")
      (value "TEST_POINT")
      (footprint "eagle-import:5015")
      (fields (field (name "MPN") "5015") (field (name "MANUFACTURER") "Keystone Electronics"))
      (libsource (lib "eagle-import") (part "TEST_POINT"))
    )
    (comp (ref "TP3")
      (value "TEST_POINT")
      (footprint "eagle-import:5015")
      (fields (field (name "MPN") "5015") (field (name "MANUFACTURER") "Keystone Electronics"))
      (libsource (lib "eagle-import") (part "TEST_POINT"))
    )
    (comp (ref "TP4")
      (value "TEST_POINT")
      (footprint "eagle-import:5015")
      (fields (field (name "MPN") "5015") (field (name "MANUFACTURER") "Keystone Electronics"))
      (libsource (lib "eagle-import") (part "TEST_POINT"))
    )
    (comp (ref "TP5")
      (value "TEST_POINT")
      (footprint "eagle-import:5015")
      (fields (field (name "MPN") "5015") (field (name "MANUFACTURER") "Keystone Electronics"))
      (libsource (lib "eagle-import") (part "TEST_POINT"))
    )
    (comp (ref "TP6")
      (value "TEST_POINT")
      (footprint "eagle-import:5015")
      (fields (field (name "MPN") "5015") (field (name "MANUFACTURER") "Keystone Electronics"))
      (libsource (lib "eagle-import") (part "TEST_POINT"))
    )
    (comp (ref "TP7")
      (value "TEST_POINT")
      (footprint "eagle-import:5015")
      (fields (field (name "MPN") "5015") (field (name "MANUFACTURER") "Keystone Electronics"))
      (libsource (lib "eagle-import") (part "TEST_POINT"))
    )
    (comp (ref "TP8")
      (value "TEST_POINT")
      (footprint "eagle-import:5015")
      (fields (field (name "MPN") "5015") (field (name "MANUFACTURER") "Keystone Electronics"))
      (libsource (lib "eagle-import") (part "TEST_POINT"))
    )
    (comp (ref "TP9")
      (value "TEST_POINT")
      (footprint "eagle-import:5015")
      (fields (field (name "MPN") "5015") (field (name "MANUFACTURER") "Keystone Electronics"))
      (libsource (lib "eagle-import") (part "TEST_POINT"))
    )
    (comp (ref "TP10")
      (value "TEST_POINT")
      (footprint "eagle-import:5015")
      (fields (field (name "MPN") "5015") (field (name "MANUFACTURER") "Keystone Electronics"))
      (libsource (lib "eagle-import") (part "TEST_POINT"))
    )
    (comp (ref "TP11")
      (value "TEST_POINT")
      (footprint "eagle-import:5015")
      (fields (field (name "MPN") "5015") (field (name "MANUFACTURER") "Keystone Electronics"))
      (libsource (lib "eagle-import") (part "TEST_POINT"))
    )
    (comp (ref "TP12")
      (value "TEST_POINT")
      (footprint "eagle-import:5015")
      (fields (field (name "MPN") "5015") (field (name "MANUFACTURER") "Keystone Electronics"))
      (libsource (lib "eagle-import") (part "TEST_POINT"))
    )
    (comp (ref "TP13")
      (value "TEST_POINT")
      (footprint "eagle-import:5015")
      (fields (field (name "MPN") "5015") (field (name "MANUFACTURER") "Keystone Electronics"))
      (libsource (lib "eagle-import") (part "TEST_POINT"))
    )
    (comp (ref "U$4")
      (value "RELAY_SOLIDSTATE_NO")
      (footprint "eagle-import:DIP-4")
      (fields (field (name "MPN") "AQY214EHA") (field (name "MANUFACTURER") "AQY214EHA"))
      (libsource (lib "eagle-import") (part "RELAY_SOLIDSTATE_NO"))
    )
  )
  (nets
    (net (code "1") (name "+5V") (class "Default")
      (node (ref "5V_PWR") (pin "2") (pinfunction "A_2") (pintype "passive"))
      (node (ref "A1") (pin "VIN") (pinfunction "VIN_VIN") (pintype "power_in"))
      (node (ref "A2") (pin "VIN") (pinfunction "VIN_VIN") (pintype "power_in"))
      (node (ref "C101") (pin "2") (pinfunction "2_2") (pintype "passive"))
      (node (ref "C103") (pin "2") (pinfunction "2_2") (pintype "passive"))
      (node (ref "C4") (pin "2") (pinfunction "2_2") (pintype "passive"))
      (node (ref "C5") (pin "1") (pinfunction "1_1") (pintype "passive"))
      (node (ref "C6") (pin "1") (pinfunction "1_1") (pintype "passive"))
      (node (ref "LATCH") (pin "2") (pinfunction "A_2") (pintype "passive"))
      (node (ref "TP12") (pin "1") (pinfunction "1_1") (pintype "passive"))
      (node (ref "U100") (pin "3") (pinfunction "VDD_3") (pintype "power_in"))
      (node (ref "U101") (pin "3") (pinfunction "VDD_3") (pintype "power_in"))
      (node (ref "U3") (pin "2") (pinfunction "OUT_2") (pintype "power_in"))
      (node (ref "U3") (pin "4") (pinfunction "OUT_4") (pintype "power_in"))
    )
    (net (code "2") (name "+12V") (class "Default")
      (node (ref "AUX_CAN") (pin "1") (pinfunction "+12V_1") (pintype "power_in"))
      (node (ref "C7") (pin "1") (pinfunction "1_1") (pintype "passive"))
      (node (ref "MAIN_CONNECTOR") (pin "4") (pinfunction "4_4") (pintype "passive"))
      (node (ref "R17") (pin "1") (pinfunction "1_1") (pintype "passive"))
      (node (ref "TP13") (pin "1") (pinfunction "1_1") (pintype "passive"))
      (node (ref "U$4") (pin "4") (pinfunction "CONTACT2_4") (pintype "bidirectional"))
      (node (ref "U3") (pin "3") (pinfunction "IN_3") (pintype "power_in"))
      (node (ref "XF1") (pin "3") (pinfunction "2_3") (pintype "passive"))
      (node (ref "XF1") (pin "4") (pinfunction "2_4") (pintype "passive"))
    )
    (net (code "3") (name "4.0_CRX") (class "Default")
      (node (ref "A2") (pin "D0") (pinfunction "(CRX1)D0_D0") (pintype "bidirectional"))
      (node (ref "A2") (pin "D4") (pinfunction "D4_D4") (pintype "bidirectional"))
      (node (ref "U100") (pin "4") (pinfunction "RXD_4") (pintype "output"))
    )
    (net (code "4") (name "4.0_CTX") (class "Default")
      (node (ref "A2") (pin "D1") (pinfunction "(CTX1)D1_D1") (pintype "bidirectional"))
      (node (ref "A2") (pin "D3") (pinfunction "D3_D3") (pintype "bidirectional"))
      (node (ref "U100") (pin "1") (pinfunction "TXD_1") (pintype "input"))
    )
    (net (code "5") (name "4.1_CRX") (class "Default")
      (node (ref "A1") (pin "D0") (pinfunction "(CRX1)D0_D0") (pintype "bidirectional"))
      (node (ref "A1") (pin "D4") (pinfunction "D4_D4") (pintype "bidirectional"))
      (node (ref "U101") (pin "4") (pinfunction "RXD_4") (pintype "output"))
    )
    (net (code "6") (name "4.1_CTX") (class "Default")
      (node (ref "A1") (pin "D1") (pinfunction "(CTX1)D1_D1") (pintype "bidirectional"))
      (node (ref "A1") (pin "D3") (pinfunction "D3_D3") (pintype "bidirectional"))
      (node (ref "U101") (pin "1") (pinfunction "TXD_1") (pintype "input"))
    )
    (net (code "7") (name "12V_READ") (class "Default")
      (node (ref "A1") (pin "D20") (pinfunction "A6_D20") (pintype "bidirectional"))
      (node (ref "A2") (pin "D20") (pinfunction "A6_D20") (pintype "bidirectional"))
      (node (ref "R10") (pin "1") (pinfunction "1_1") (pintype "passive"))
      (node (ref "R17") (pin "2") (pinfunction "2_2") (pintype "passive"))
    )
    (net (code "8") (name "BMS_OK") (class "Default")
      (node (ref "BMS_OK") (pin "2") (pinfunction "A_2") (pintype "passive"))
      (node (ref "D101") (pin "3") (pinfunction "C_3") (pintype "passive"))
      (node (ref "MAIN_CONNECTOR") (pin "6") (pinfunction "6_6") (pintype "passive"))
      (node (ref "R33") (pin "2") (pinfunction "2_2") (pintype "passive"))
      (node (ref "R34") (pin "2") (pinfunction "2_2") (pintype "passive"))
      (node (ref "TP7") (pin "1") (pinfunction "1_1") (pintype "passive"))
    )
    (net (code "9") (name "CANH") (class "Default")
      (node (ref "AUX_CAN") (pin "4") (pinfunction "CANH_4") (pintype "bidirectional"))
      (node (ref "CAN_TERM") (pin "2") (pinfunction "2_2") (pintype "passive"))
      (node (ref "CHG_CAN") (pin "4") (pinfunction "4_4") (pintype "passive"))
      (node (ref "D100") (pin "1") (pinfunction "C1_1") (pintype "passive"))
      (node (ref "MAIN_CONNECTOR") (pin "1") (pinfunction "1_1") (pintype "passive"))
      (node (ref "U100") (pin "7") (pinfunction "CANH_7") (pintype "bidirectional"))
      (node (ref "U101") (pin "7") (pinfunction "CANH_7") (pintype "bidirectional"))
    )
    (net (code "10") (name "CANL") (class "Default")
      (node (ref "AUX_CAN") (pin "3") (pinfunction "CANL_3") (pintype "bidirectional"))
      (node (ref "CHG_CAN") (pin "5") (pinfunction "5_5") (pintype "passive"))
      (node (ref "D100") (pin "2") (pinfunction "C2_2") (pintype "passive"))
      (node (ref "MAIN_CONNECTOR") (pin "2") (pinfunction "2_2") (pintype "passive"))
      (node (ref "R40") (pin "1") (pinfunction "1_1") (pintype "passive"))
      (node (ref "U100") (pin "6") (pinfunction "CANL_6") (pintype "bidirectional"))
      (node (ref "U101") (pin "6") (pinfunction "CANL_6") (pintype "bidirectional"))
    )
    (net (code "11") (name "CCU_OK") (class "Default")
      (node (ref "CCU_OK") (pin "2") (pinfunction "A_2") (pintype "passive"))
      (node (ref "R30") (pin "2") (pinfunction "2_2") (pintype "passive"))
      (node (ref "R31") (pin "2") (pinfunction "2_2") (pintype "passive"))
      (node (ref "TP9") (pin "1") (pinfunction "1_1") (pintype "passive"))
      (node (ref "U1") (pin "4") (pinfunction "OUT_4") (pintype "output"))
    )
    (net (code "12") (name "GND") (class "Default")
      (node (ref "A1") (pin "AGND/GND") (pinfunction "GND_AGND/GND") (pintype "bidirectional"))
      (node (ref "A1") (pin "GND") (pinfunction "GND_GND") (pintype "bidirectional"))
      (node (ref "A1") (pin "GND@2") (pinfunction "GND_GND@2") (pintype "bidirectional"))
      (node (ref "A2") (pin "AGND/GND") (pinfunction "GND_AGND/GND") (pintype "power_in"))
      (node (ref "A2") (pin "GND") (pinfunction "GND_GND") (pintype "power_in"))
      (node (ref "AUX_CAN") (pin "2") (pinfunction "GND_2") (pintype "power_in"))
      (node (ref "C1") (pin "1") (pinfunction "1_1") (pintype "passive"))
      (node (ref "C100") (pin "1") (pinfunction "1_1") (pintype "passive"))
      (node (ref "C101") (pin "1") (pinfunction "1_1") (pintype "passive"))
      (node (ref "C102") (pin "1") (pinfunction "1_1") (pintype "passive"))
      (node (ref "C103") (pin "1") (pinfunction "1_1") (pintype "passive"))
      (node (ref "C2") (pin "1") (pinfunction "1_1") (pintype "passive"))
      (node (ref "C3") (pin "1") (pinfunction "1_1") (pintype "passive"))
      (node (ref "C4") (pin "1") (pinfunction "1_1") (pintype "passive"))
      (node (ref "C5") (pin "2") (pinfunction "2_2") (pintype "passive"))
      (node (ref "C6") (pin "2") (pinfunction "2_2") (pintype "passive"))
      (node (ref "C7") (pin "2") (pinfunction "2_2") (pintype "passive"))
      (node (ref "C8") (pin "2") (pinfunction "2_2") (pintype "passive"))
      (node (ref "CHG_CAN") (pin "6") (pinfunction "6_6") (pintype "passive"))
      (node (ref "D100") (pin "3") (pinfunction "A_3") (pintype "passive"))
      (node (ref "D101") (pin "1") (pinfunction "A_1") (pintype "passive"))
      (node (ref "D102") (pin "1") (pinfunction "A_1") (pintype "passive"))
      (node (ref "D3") (pin "1") (pinfunction "C_1") (pintype "passive"))
      (node (ref "D5") (pin "1") (pinfunction "A_1") (pintype "passive"))
      (node (ref "K1") (pin "14") (pinfunction "4_14") (pintype "bidirectional"))
      (node (ref "K2") (pin "14") (pinfunction "4_14") (pintype "bidirectional"))
      (node (ref "K3") (pin "14") (pinfunction "4_14") (pintype "bidirectional"))
      (node (ref "LATCH_BUTTON") (pin "3") (pinfunction "S_3") (pintype "passive"))
      (node (ref "LATCH_BUTTON") (pin "4") (pinfunction "S_4") (pintype "passive"))
      (node (ref "MAIN_CONNECTOR") (pin "3") (pinfunction "3_3") (pintype "passive"))
      (node (ref "POWER") (pin "2") (pinfunction "2_2") (pintype "passive"))
      (node (ref "R1") (pin "2") (pinfunction "2_2") (pintype "passive"))
      (node (ref "R10") (pin "2") (pinfunction "2_2") (pintype "passive"))
      (node (ref "R11") (pin "2") (pinfunction "2_2") (pintype "passive"))
      (node (ref "R12") (pin "2") (pinfunction "2_2") (pintype "passive"))
      (node (ref "R13") (pin "2") (pinfunction "2_2") (pintype "passive"))
      (node (ref "R14") (pin "2") (pinfunction "2_2") (pintype "passive"))
      (node (ref "R15") (pin "2") (pinfunction "2_2") (pintype "passive"))
      (node (ref "R16") (pin "2") (pinfunction "2_2") (pintype "passive"))
      (node (ref "R2") (pin "2") (pinfunction "2_2") (pintype "passive"))
      (node (ref "R24") (pin "1") (pinfunction "1_1") (pintype "passive"))
      (node (ref "R26") (pin "2") (pinfunction "2_2") (pintype "passive"))
      (node (ref "R27") (pin "2") (pinfunction "2_2") (pintype "passive"))
      (node (ref "R28") (pin "2") (pinfunction "2_2") (pintype "passive"))
      (node (ref "R29") (pin "1") (pinfunction "1_1") (pintype "passive"))
      (node (ref "R30") (pin "1") (pinfunction "1_1") (pintype "passive"))
      (node (ref "R32") (pin "2") (pinfunction "2_2") (pintype "passive"))
      (node (ref "R33") (pin "1") (pinfunction "1_1") (pintype "passive"))
      (node (ref "R36") (pin "1") (pinfunction "1_1") (pintype "passive"))
      (node (ref "R7") (pin "2") (pinfunction "2_2") (pintype "passive"))
      (node (ref "R8") (pin "2") (pinfunction "2_2") (pintype "passive"))
      (node (ref "R9") (pin "2") (pinfunction "2_2") (pintype "passive"))
      (node (ref "SHDN_B") (pin "1") (pinfunction "C_1") (pintype "passive"))
      (node (ref "SHDN_C") (pin "1") (pinfunction "C_1") (pintype "passive"))
      (node (ref "SHDN_D") (pin "1") (pinfunction "C_1") (pintype "passive"))
      (node (ref "SHDN_E") (pin "1") (pinfunction "C_1") (pintype "passive"))
      (node (ref "TP1") (pin "1") (pinfunction "1_1") (pintype "passive"))
      (node (ref "U$100") (pin "2") (pinfunction "CONTROL-_2") (pintype "passive"))
      (node (ref "U$100") (pin "3") (pinfunction "CONTACT1_3") (pintype "bidirectional"))
      (node (ref "U$4") (pin "2") (pinfunction "CONTROL-_2") (pintype "passive"))
      (node (ref "U1") (pin "3") (pinfunction "GND_3") (pintype "power_in"))
      (node (ref "U100") (pin "2") (pinfunction "GND_2") (pintype "power_in"))
      (node (ref "U100") (pin "8") (pinfunction "STBY_8") (pintype "passive"))
      (node (ref "U101") (pin "2") (pinfunction "GND_2") (pintype "power_in"))
      (node (ref "U101") (pin "8") (pinfunction "STBY_8") (pintype "passive"))
      (node (ref "U2") (pin "2") (pinfunction "GND_2") (pintype "power_in"))
      (node (ref "U3") (pin "1") (pinfunction "GND_1") (pintype "power_in"))
      (node (ref "XB1") (pin "2") (pinfunction "MINUS_2") (pintype "power_in"))
    )
    (net (code "13") (name "IMD_OK") (class "Default")
      (node (ref "D102") (pin "3") (pinfunction "C_3") (pintype "passive"))
      (node (ref "MAIN_CONNECTOR") (pin "5") (pinfunction "5_5") (pintype "passive"))
      (node (ref "OKHS") (pin "2") (pinfunction "A_2") (pintype "passive"))
      (node (ref "R24") (pin "2") (pinfunction "2_2") (pintype "passive"))
      (node (ref "R25") (pin "2") (pinfunction "2_2") (pintype "passive"))
      (node (ref "TP8") (pin "1") (pinfunction "1_1") (pintype "passive"))
    )
    (net (code "14") (name "LATCH_BUTTON") (class "Default")
      (node (ref "D1") (pin "C") (pinfunction "C_C") (pintype "passive"))
      (node (ref "D2") (pin "C") (pinfunction "C_C") (pintype "passive"))
      (node (ref "D4") (pin "C") (pinfunction "C_C") (pintype "passive"))
      (node (ref "LATCH_BUTTON") (pin "1") (pinfunction "P_1") (pintype "passive"))
      (node (ref "LATCH_BUTTON") (pin "2") (pinfunction "P_2") (pintype "passive"))
      (node (ref "R35") (pin "2") (pinfunction "2_2") (pintype "passive"))
    )
    (net (code "15") (name "Net-(4.1_ONLY-Pad1)") (class "Default")
      (node (ref "4.1_ONLY") (pin "1") (pinfunction "1_1") (pintype "passive"))
      (node (ref "A1") (pin "3V3") (pinfunction "3.3V_3V3") (pintype "power_in"))
      (node (ref "A1") (pin "3V3@2") (pinfunction "3.3V_3V3@2") (pintype "power_in"))
      (node (ref "A1") (pin "3V3@3") (pinfunction "3.3V_3V3@3") (pintype "power_in"))
    )
    (net (code "16") (name "Net-(5V_PWR-C)") (class "Default")
      (node (ref "5V_PWR") (pin "1") (pinfunction "C_1") (pintype "passive"))
      (node (ref "R32") (pin "1") (pinfunction "1_1") (pintype "passive"))
    )
    (net (code "17") (name "Net-(BMS_OK-C)") (class "Default")
      (node (ref "BMS_OK") (pin "1") (pinfunction "C_1") (pintype "passive"))
      (node (ref "R2") (pin "1") (pinfunction "1_1") (pintype "passive"))
    )
    (net (code "18") (name "Net-(C8-Pad1)") (class "Default")
      (node (ref "C8") (pin "1") (pinfunction "1_1") (pintype "passive"))
      (node (ref "R39") (pin "1") (pinfunction "1_1") (pintype "passive"))
      (node (ref "R40") (pin "2") (pinfunction "2_2") (pintype "passive"))
    )
    (net (code "19") (name "Net-(CAN_TERM-Pad1)") (class "Default")
      (node (ref "CAN_TERM") (pin "1") (pinfunction "1_1") (pintype "passive"))
      (node (ref "R39") (pin "2") (pinfunction "2_2") (pintype "passive"))
    )
    (net (code "20") (name "Net-(CCU_OK-C)") (class "Default")
      (node (ref "CCU_OK") (pin "1") (pinfunction "C_1") (pintype "passive"))
      (node (ref "R9") (pin "1") (pinfunction "1_1") (pintype "passive"))
    )
    (net (code "21") (name "Net-(D3-A)") (class "Default")
      (node (ref "D3") (pin "2") (pinfunction "A_2") (pintype "passive"))
      (node (ref "R38") (pin "2") (pinfunction "2_2") (pintype "passive"))
    )
    (net (code "22") (name "Net-(D5-C)") (class "Default")
      (node (ref "D5") (pin "3") (pinfunction "C_3") (pintype "passive"))
      (node (ref "POWER") (pin "1") (pinfunction "1_1") (pintype "passive"))
      (node (ref "XF1") (pin "1") (pinfunction "1_1") (pintype "passive"))
      (node (ref "XF1") (pin "2") (pinfunction "1_2") (pintype "passive"))
      (node (ref "XF2") (pin "1") (pinfunction "1_1") (pintype "passive"))
      (node (ref "XF2") (pin "2") (pinfunction "1_2") (pintype "passive"))
    )
    (net (code "23") (name "Net-(E_SELECT-Pad2)") (class "Default")
      (node (ref "E_SELECT") (pin "2") (pinfunction "2_2") (pintype "passive"))
      (node (ref "F_SELECT") (pin "2") (pinfunction "2_2") (pintype "passive"))
      (node (ref "R100") (pin "1") (pinfunction "1_1") (pintype "passive"))
    )
    (net (code "24") (name "Net-(K1-3)") (class "Default")
      (node (ref "D1") (pin "A") (pinfunction "A_A") (pintype "passive"))
      (node (ref "D105") (pin "A") (pinfunction "A_A") (pintype "passive"))
      (node (ref "K1") (pin "11") (pinfunction "3_11") (pintype "bidirectional"))
      (node (ref "K1") (pin "A2") (pinfunction "COIL-_A2") (pintype "bidirectional"))
    )
    (net (code "25") (name "Net-(K1-COIL+)") (class "Default")
      (node (ref "D105") (pin "C") (pinfunction "C_C") (pintype "passive"))
      (node (ref "K1") (pin "A1") (pinfunction "COIL+_A1") (pintype "bidirectional"))
      (node (ref "R25") (pin "1") (pinfunction "1_1") (pintype "passive"))
    )
    (net (code "26") (name "Net-(K2-3)") (class "Default")
      (node (ref "D104") (pin "A") (pinfunction "A_A") (pintype "passive"))
      (node (ref "D2") (pin "A") (pinfunction "A_A") (pintype "passive"))
      (node (ref "K2") (pin "11") (pinfunction "3_11") (pintype "bidirectional"))
      (node (ref "K2") (pin "A2") (pinfunction "COIL-_A2") (pintype "bidirectional"))
    )
    (net (code "27") (name "Net-(K2-COIL+)") (class "Default")
      (node (ref "D104") (pin "C") (pinfunction "C_C") (pintype "passive"))
      (node (ref "K2") (pin "A1") (pinfunction "COIL+_A1") (pintype "bidirectional"))
      (node (ref "R34") (pin "1") (pinfunction "1_1") (pintype "passive"))
    )
    (net (code "28") (name "Net-(K3-3)") (class "Default")
      (node (ref "D103") (pin "A") (pinfunction "A_A") (pintype "passive"))
      (node (ref "D4") (pin "A") (pinfunction "A_A") (pintype "passive"))
      (node (ref "K3") (pin "11") (pinfunction "3_11") (pintype "bidirectional"))
      (node (ref "K3") (pin "A2") (pinfunction "COIL-_A2") (pintype "bidirectional"))
    )
    (net (code "29") (name "Net-(K3-COIL+)") (class "Default")
      (node (ref "D103") (pin "C") (pinfunction "C_C") (pintype "passive"))
      (node (ref "K3") (pin "A1") (pinfunction "COIL+_A1") (pintype "bidirectional"))
      (node (ref "R37") (pin "1") (pinfunction "1_1") (pintype "passive"))
    )
    (net (code "30") (name "Net-(LATCH-C)") (class "Default")
      (node (ref "LATCH") (pin "1") (pinfunction "C_1") (pintype "passive"))
      (node (ref "R35") (pin "1") (pinfunction "1_1") (pintype "passive"))
    )
    (net (code "31") (name "Net-(OKHS-C)") (class "Default")
      (node (ref "OKHS") (pin "1") (pinfunction "C_1") (pintype "passive"))
      (node (ref "R7") (pin "1") (pinfunction "1_1") (pintype "passive"))
    )
    (net (code "32") (name "Net-(SHDN_B-A)") (class "Default")
      (node (ref "R3") (pin "2") (pinfunction "2_2") (pintype "passive"))
      (node (ref "SHDN_B") (pin "2") (pinfunction "A_2") (pintype "passive"))
    )
    (net (code "33") (name "Net-(SHDN_C-A)") (class "Default")
      (node (ref "R4") (pin "2") (pinfunction "2_2") (pintype "passive"))
      (node (ref "SHDN_C") (pin "2") (pinfunction "A_2") (pintype "passive"))
    )
    (net (code "34") (name "Net-(SHDN_D-A)") (class "Default")
      (node (ref "R5") (pin "2") (pinfunction "2_2") (pintype "passive"))
      (node (ref "SHDN_D") (pin "2") (pinfunction "A_2") (pintype "passive"))
    )
    (net (code "35") (name "Net-(SHDN_E-A)") (class "Default")
      (node (ref "R6") (pin "2") (pinfunction "2_2") (pintype "passive"))
      (node (ref "SHDN_E") (pin "2") (pinfunction "A_2") (pintype "passive"))
    )
    (net (code "36") (name "Net-(SHDN_F-C)") (class "Default")
      (node (ref "R8") (pin "1") (pinfunction "1_1") (pintype "passive"))
      (node (ref "SHDN_F") (pin "1") (pinfunction "C_1") (pintype "passive"))
    )
    (net (code "37") (name "Net-(STATUS_4.0-C)") (class "Default")
      (node (ref "R26") (pin "1") (pinfunction "1_1") (pintype "passive"))
      (node (ref "STATUS_4.0") (pin "1") (pinfunction "C_1") (pintype "passive"))
    )
    (net (code "38") (name "Net-(STATUS_4.1-C)") (class "Default")
      (node (ref "R1") (pin "1") (pinfunction "1_1") (pintype "passive"))
      (node (ref "STATUS_4.1") (pin "1") (pinfunction "C_1") (pintype "passive"))
    )
    (net (code "39") (name "Net-(U$4-CONTACT1)") (class "Default")
      (node (ref "R36") (pin "2") (pinfunction "2_2") (pintype "passive"))
      (node (ref "R37") (pin "2") (pinfunction "2_2") (pintype "passive"))
      (node (ref "R38") (pin "1") (pinfunction "1_1") (pintype "passive"))
      (node (ref "U$4") (pin "3") (pinfunction "CONTACT1_3") (pintype "bidirectional"))
    )
    (net (code "40") (name "Net-(U$4-CONTROL+)") (class "Default")
      (node (ref "R31") (pin "1") (pinfunction "1_1") (pintype "passive"))
      (node (ref "U$4") (pin "1") (pinfunction "CONTROL+_1") (pintype "passive"))
    )
    (net (code "41") (name "Net-(U$100-CONTROL+)") (class "Default")
      (node (ref "R100") (pin "2") (pinfunction "2_2") (pintype "passive"))
      (node (ref "U$100") (pin "1") (pinfunction "CONTROL+_1") (pintype "passive"))
    )
    (net (code "42") (name "Net-(U1A-IN)") (class "Default")
      (node (ref "R27") (pin "1") (pinfunction "1_1") (pintype "passive"))
      (node (ref "U1") (pin "2") (pinfunction "IN_2") (pintype "input"))
      (node (ref "U2") (pin "1") (pinfunction "~{RESET}_1") (pintype "output"))
    )
    (net (code "43") (name "Net-(XB1-PLUS)") (class "Default")
      (node (ref "A1") (pin "VBAT") (pinfunction "VBAT_VBAT") (pintype "power_in"))
      (node (ref "XB1") (pin "1") (pinfunction "PLUS_1") (pintype "power_in"))
    )
    (net (code "44") (name "RPC_SWITCH") (class "Default")
      (node (ref "MAIN_CONNECTOR") (pin "8") (pinfunction "8_8") (pintype "passive"))
      (node (ref "U$100") (pin "4") (pinfunction "CONTACT2_4") (pintype "bidirectional"))
    )
    (net (code "45") (name "SHDN_A") (class "Default")
      (node (ref "K1") (pin "21") (pinfunction "6_21") (pintype "bidirectional"))
      (node (ref "R23") (pin "1") (pinfunction "1_1") (pintype "passive"))
      (node (ref "TP10") (pin "1") (pinfunction "1_1") (pintype "passive"))
      (node (ref "XF2") (pin "3") (pinfunction "2_3") (pintype "passive"))
      (node (ref "XF2") (pin "4") (pinfunction "2_4") (pintype "passive"))
    )
    (net (code "46") (name "SHDN_A_READ") (class "Default")
      (node (ref "A1") (pin "D14") (pinfunction "A0_D14") (pintype "bidirectional"))
      (node (ref "A2") (pin "D14") (pinfunction "A0_D14") (pintype "bidirectional"))
      (node (ref "R16") (pin "1") (pinfunction "1_1") (pintype "passive"))
      (node (ref "R23") (pin "2") (pinfunction "2_2") (pintype "passive"))
    )
    (net (code "47") (name "SHDN_B") (class "Default")
      (node (ref "K1") (pin "24") (pinfunction "5_24") (pintype "bidirectional"))
      (node (ref "K2") (pin "21") (pinfunction "6_21") (pintype "bidirectional"))
      (node (ref "R22") (pin "1") (pinfunction "1_1") (pintype "passive"))
      (node (ref "R3") (pin "1") (pinfunction "1_1") (pintype "passive"))
      (node (ref "TP2") (pin "1") (pinfunction "1_1") (pintype "passive"))
    )
    (net (code "48") (name "SHDN_B_READ") (class "Default")
      (node (ref "A1") (pin "D15") (pinfunction "A1_D15") (pintype "bidirectional"))
      (node (ref "A2") (pin "D15") (pinfunction "A1_D15") (pintype "bidirectional"))
      (node (ref "R15") (pin "1") (pinfunction "1_1") (pintype "passive"))
      (node (ref "R22") (pin "2") (pinfunction "2_2") (pintype "passive"))
    )
    (net (code "49") (name "SHDN_C") (class "Default")
      (node (ref "K2") (pin "24") (pinfunction "5_24") (pintype "bidirectional"))
      (node (ref "K3") (pin "21") (pinfunction "6_21") (pintype "bidirectional"))
      (node (ref "R21") (pin "1") (pinfunction "1_1") (pintype "passive"))
      (node (ref "R4") (pin "1") (pinfunction "1_1") (pintype "passive"))
      (node (ref "TP3") (pin "1") (pinfunction "1_1") (pintype "passive"))
    )
    (net (code "50") (name "SHDN_C_READ") (class "Default")
      (node (ref "A1") (pin "D16") (pinfunction "A2_D16") (pintype "bidirectional"))
      (node (ref "A2") (pin "D16") (pinfunction "A2_D16") (pintype "bidirectional"))
      (node (ref "R14") (pin "1") (pinfunction "1_1") (pintype "passive"))
      (node (ref "R21") (pin "2") (pinfunction "2_2") (pintype "passive"))
    )
    (net (code "51") (name "SHDN_D") (class "Default")
      (node (ref "K3") (pin "24") (pinfunction "5_24") (pintype "bidirectional"))
      (node (ref "R20") (pin "1") (pinfunction "1_1") (pintype "passive"))
      (node (ref "R5") (pin "1") (pinfunction "1_1") (pintype "passive"))
      (node (ref "SHDN_BTN") (pin "1") (pinfunction "1_1") (pintype "passive"))
      (node (ref "TP4") (pin "1") (pinfunction "1_1") (pintype "passive"))
    )
    (net (code "52") (name "SHDN_D_READ") (class "Default")
      (node (ref "A1") (pin "D17") (pinfunction "A3_D17") (pintype "bidirectional"))
      (node (ref "A2") (pin "D17") (pinfunction "A3_D17") (pintype "bidirectional"))
      (node (ref "R13") (pin "1") (pinfunction "1_1") (pintype "passive"))
      (node (ref "R20") (pin "2") (pinfunction "2_2") (pintype "passive"))
    )
    (net (code "53") (name "SHDN_E") (class "Default")
      (node (ref "CHG_CAN") (pin "3") (pinfunction "3_3") (pintype "passive"))
      (node (ref "E_SELECT") (pin "1") (pinfunction "1_1") (pintype "passive"))
      (node (ref "R19") (pin "1") (pinfunction "1_1") (pintype "passive"))
      (node (ref "R6") (pin "1") (pinfunction "1_1") (pintype "passive"))
      (node (ref "SHDN_BTN") (pin "2") (pinfunction "2_2") (pintype "passive"))
      (node (ref "TP5") (pin "1") (pinfunction "1_1") (pintype "passive"))
    )
    (net (code "54") (name "SHDN_E_READ") (class "Default")
      (node (ref "A1") (pin "D18") (pinfunction "A4_D18") (pintype "bidirectional"))
      (node (ref "A2") (pin "D18") (pinfunction "A4_D18") (pintype "bidirectional"))
      (node (ref "R12") (pin "1") (pinfunction "1_1") (pintype "passive"))
      (node (ref "R19") (pin "2") (pinfunction "2_2") (pintype "passive"))
    )
    (net (code "55") (name "SHDN_F") (class "Default")
      (node (ref "CHG_CAN") (pin "2") (pinfunction "2_2") (pintype "passive"))
      (node (ref "F_SELECT") (pin "1") (pinfunction "1_1") (pintype "passive"))
      (node (ref "MAIN_CONNECTOR") (pin "7") (pinfunction "7_7") (pintype "passive"))
      (node (ref "R18") (pin "1") (pinfunction "1_1") (pintype "passive"))
      (node (ref "SHDN_F") (pin "2") (pinfunction "A_2") (pintype "passive"))
      (node (ref "TP6") (pin "1") (pinfunction "1_1") (pintype "passive"))
    )
    (net (code "56") (name "SHDN_F_READ") (class "Default")
      (node (ref "A1") (pin "D19") (pinfunction "A5_D19") (pintype "bidirectional"))
      (node (ref "A2") (pin "D19") (pinfunction "A5_D19") (pintype "bidirectional"))
      (node (ref "R11") (pin "1") (pinfunction "1_1") (pintype "passive"))
      (node (ref "R18") (pin "2") (pinfunction "2_2") (pintype "passive"))
    )
    (net (code "57") (name "STATUS_4.0") (class "Default")
      (node (ref "A2") (pin "D5") (pinfunction "D5_D5") (pintype "bidirectional"))
      (node (ref "STATUS_4.0") (pin "2") (pinfunction "A_2") (pintype "passive"))
    )
    (net (code "58") (name "STATUS_4.1") (class "Default")
      (node (ref "A1") (pin "D5") (pinfunction "D5_D5") (pintype "bidirectional"))
      (node (ref "STATUS_4.1") (pin "2") (pinfunction "A_2") (pintype "passive"))
    )
    (net (code "59") (name "SW_SHUTDOWN") (class "Default")
      (node (ref "A1") (pin "D6") (pinfunction "D6_D6") (pintype "bidirectional"))
      (node (ref "A2") (pin "D6") (pinfunction "D6_D6") (pintype "bidirectional"))
      (node (ref "C1") (pin "2") (pinfunction "2_2") (pintype "passive"))
      (node (ref "R29") (pin "2") (pinfunction "2_2") (pintype "passive"))
      (node (ref "U2") (pin "3") (pinfunction "~{MR}_3") (pintype "input"))
    )
    (net (code "60") (name "VDD") (class "Default")
      (node (ref "4.1_ONLY") (pin "2") (pinfunction "2_2") (pintype "passive"))
      (node (ref "A2") (pin "3.3V") (pinfunction "3.3V_3.3V") (pintype "power_in"))
      (node (ref "C100") (pin "2") (pinfunction "2_2") (pintype "passive"))
      (node (ref "C102") (pin "2") (pinfunction "2_2") (pintype "passive"))
      (node (ref "C2") (pin "2") (pinfunction "2_2") (pintype "passive"))
      (node (ref "C3") (pin "2") (pinfunction "2_2") (pintype "passive"))
      (node (ref "TP11") (pin "1") (pinfunction "1_1") (pintype "passive"))
      (node (ref "U1") (pin "5") (pinfunction "VDD_5") (pintype "power_in"))
      (node (ref "U100") (pin "5") (pinfunction "VIO_5") (pintype "power_in"))
      (node (ref "U101") (pin "5") (pinfunction "VIO_5") (pintype "power_in"))
      (node (ref "U2") (pin "5") (pinfunction "VDD_5") (pintype "power_in"))
    )
    (net (code "61") (name "WATCHDOG_IN") (class "Default")
      (node (ref "A1") (pin "D7") (pinfunction "D7_D7") (pintype "bidirectional"))
      (node (ref "A2") (pin "D7") (pinfunction "D7_D7") (pintype "bidirectional"))
      (node (ref "R28") (pin "1") (pinfunction "1_1") (pintype "passive"))
      (node (ref "U2") (pin "4") (pinfunction "WDI_4") (pintype "input"))
    )
    (net (code "62") (name "unconnected-(A1-(CLK)D13-PadD13)") (class "Default")
      (node (ref "A1") (pin "D13") (pinfunction "(CLK)D13_D13") (pintype "bidirectional"))
    )
    (net (code "63") (name "unconnected-(A1-(CS)D10-PadD10)") (class "Default")
      (node (ref "A1") (pin "D10") (pinfunction "(CS)D10_D10") (pintype "bidirectional"))
    )
    (net (code "64") (name "unconnected-(A1-(SDI)D12-PadD12)") (class "Default")
      (node (ref "A1") (pin "D12") (pinfunction "(SDI)D12_D12") (pintype "bidirectional"))
    )
    (net (code "65") (name "unconnected-(A1-(SDO)D11-PadD11)") (class "Default")
      (node (ref "A1") (pin "D11") (pinfunction "(SDO)D11_D11") (pintype "bidirectional"))
    )
    (net (code "66") (name "unconnected-(A1-A7-PadD21)") (class "Default")
      (node (ref "A1") (pin "D21") (pinfunction "A7_D21") (pintype "bidirectional"))
    )
    (net (code "67") (name "unconnected-(A1-A8-PadD22)") (class "Default")
      (node (ref "A1") (pin "D22") (pinfunction "A8_D22") (pintype "bidirectional"))
    )
    (net (code "68") (name "unconnected-(A1-A9-PadD23)") (class "Default")
      (node (ref "A1") (pin "D23") (pinfunction "A9_D23") (pintype "bidirectional"))
    )
    (net (code "69") (name "unconnected-(A1-A10-PadD24)") (class "Default")
      (node (ref "A1") (pin "D24") (pinfunction "A10_D24") (pintype "bidirectional"))
    )
    (net (code "70") (name "unconnected-(A1-A11-PadD25)") (class "Default")
      (node (ref "A1") (pin "D25") (pinfunction "A11_D25") (pintype "bidirectional"))
    )
    (net (code "71") (name "unconnected-(A1-A12-PadD26)") (class "Default")
      (node (ref "A1") (pin "D26") (pinfunction "A12_D26") (pintype "bidirectional"))
    )
    (net (code "72") (name "unconnected-(A1-A13-PadD27)") (class "Default")
      (node (ref "A1") (pin "D27") (pinfunction "A13_D27") (pintype "bidirectional"))
    )
    (net (code "73") (name "unconnected-(A1-A14-PadD38)") (class "Default")
      (node (ref "A1") (pin "D38") (pinfunction "A14_D38") (pintype "bidirectional"))
    )
    (net (code "74") (name "unconnected-(A1-A15-PadD39)") (class "Default")
      (node (ref "A1") (pin "D39") (pinfunction "A15_D39") (pintype "bidirectional"))
    )
    (net (code "75") (name "unconnected-(A1-A16-PadD40)") (class "Default")
      (node (ref "A1") (pin "D40") (pinfunction "A16_D40") (pintype "bidirectional"))
    )
    (net (code "76") (name "unconnected-(A1-A17-PadD41)") (class "Default")
      (node (ref "A1") (pin "D41") (pinfunction "A17_D41") (pintype "bidirectional"))
    )
    (net (code "77") (name "unconnected-(A1-PadD2)") (class "Default")
      (node (ref "A1") (pin "D2") (pinfunction "D2_D2") (pintype "bidirectional"))
    )
    (net (code "78") (name "unconnected-(A1-PadD8)") (class "Default")
      (node (ref "A1") (pin "D8") (pinfunction "D8_D8") (pintype "bidirectional"))
    )
    (net (code "79") (name "unconnected-(A1-PadD9)") (class "Default")
      (node (ref "A1") (pin "D9") (pinfunction "D9_D9") (pintype "bidirectional"))
    )
    (net (code "80") (name "unconnected-(A1-PadD28)") (class "Default")
      (node (ref "A1") (pin "D28") (pinfunction "D28_D28") (pintype "bidirectional"))
    )
    (net (code "81") (name "unconnected-(A1-PadD29)") (class "Default")
      (node (ref "A1") (pin "D29") (pinfunction "D29_D29") (pintype "bidirectional"))
    )
    (net (code "82") (name "unconnected-(A1-PadD30)") (class "Default")
      (node (ref "A1") (pin "D30") (pinfunction "D30_D30") (pintype "bidirectional"))
    )
    (net (code "83") (name "unconnected-(A1-PadD31)") (class "Default")
      (node (ref "A1") (pin "D31") (pinfunction "D31_D31") (pintype "bidirectional"))
    )
    (net (code "84") (name "unconnected-(A1-PadD32)") (class "Default")
      (node (ref "A1") (pin "D32") (pinfunction "D32_D32") (pintype "bidirectional"))
    )
    (net (code "85") (name "unconnected-(A1-PadD33)") (class "Default")
      (node (ref "A1") (pin "D33") (pinfunction "D33_D33") (pintype "bidirectional"))
    )
    (net (code "86") (name "unconnected-(A1-PadD34)") (class "Default")
      (node (ref "A1") (pin "D34") (pinfunction "D34_D34") (pintype "bidirectional"))
    )
    (net (code "87") (name "unconnected-(A1-PadD35)") (class "Default")
      (node (ref "A1") (pin "D35") (pinfunction "D35_D35") (pintype "bidirectional"))
    )
    (net (code "88") (name "unconnected-(A1-PadD36)") (class "Default")
      (node (ref "A1") (pin "D36") (pinfunction "D36_D36") (pintype "bidirectional"))
    )
    (net (code "89") (name "unconnected-(A1-PadD37)") (class "Default")
      (node (ref "A1") (pin "D37") (pinfunction "D37_D37") (pintype "bidirectional"))
    )
    (net (code "90") (name "unconnected-(A2-(CLK)D13-PadD13)") (class "Default")
      (node (ref "A2") (pin "D13") (pinfunction "(CLK)D13_D13") (pintype "bidirectional"))
    )
    (net (code "91") (name "unconnected-(A2-(CS)D10-PadD10)") (class "Default")
      (node (ref "A2") (pin "D10") (pinfunction "(CS)D10_D10") (pintype "bidirectional"))
    )
    (net (code "92") (name "unconnected-(A2-(SDI)D12-PadD12)") (class "Default")
      (node (ref "A2") (pin "D12") (pinfunction "(SDI)D12_D12") (pintype "bidirectional"))
    )
    (net (code "93") (name "unconnected-(A2-(SDO)D11-PadD11)") (class "Default")
      (node (ref "A2") (pin "D11") (pinfunction "(SDO)D11_D11") (pintype "bidirectional"))
    )
    (net (code "94") (name "unconnected-(A2-A7-PadD21)") (class "Default")
      (node (ref "A2") (pin "D21") (pinfunction "A7_D21") (pintype "bidirectional"))
    )
    (net (code "95") (name "unconnected-(A2-A8-PadD22)") (class "Default")
      (node (ref "A2") (pin "D22") (pinfunction "A8_D22") (pintype "bidirectional"))
    )
    (net (code "96") (name "unconnected-(A2-A9-PadD23)") (class "Default")
      (node (ref "A2") (pin "D23") (pinfunction "A9_D23") (pintype "bidirectional"))
    )
    (net (code "97") (name "unconnected-(A2-PadD2)") (class "Default")
      (node (ref "A2") (pin "D2") (pinfunction "D2_D2") (pintype "bidirectional"))
    )
    (net (code "98") (name "unconnected-(A2-PadD8)") (class "Default")
      (node (ref "A2") (pin "D8") (pinfunction "D8_D8") (pintype "bidirectional"))
    )
    (net (code "99") (name "unconnected-(A2-PadD9)") (class "Default")
      (node (ref "A2") (pin "D9") (pinfunction "D9_D9") (pintype "bidirectional"))
    )
    (net (code "100") (name "unconnected-(CHG_CAN-Pad1)") (class "Default")
      (node (ref "CHG_CAN") (pin "1") (pinfunction "1_1") (pintype "passive"))
    )
    (net (code "101") (name "unconnected-(K1-2-Pad12)") (class "Default")
      (node (ref "K1") (pin "12") (pinfunction "2_12") (pintype "bidirectional"))
    )
    (net (code "102") (name "unconnected-(K1-7-Pad22)") (class "Default")
      (node (ref "K1") (pin "22") (pinfunction "7_22") (pintype "bidirectional"))
    )
    (net (code "103") (name "unconnected-(K2-2-Pad12)") (class "Default")
      (node (ref "K2") (pin "12") (pinfunction "2_12") (pintype "bidirectional"))
    )
    (net (code "104") (name "unconnected-(K2-7-Pad22)") (class "Default")
      (node (ref "K2") (pin "22") (pinfunction "7_22") (pintype "bidirectional"))
    )
    (net (code "105") (name "unconnected-(K3-2-Pad12)") (class "Default")
      (node (ref "K3") (pin "12") (pinfunction "2_12") (pintype "bidirectional"))
    )
    (net (code "106") (name "unconnected-(K3-7-Pad22)") (class "Default")
      (node (ref "K3") (pin "22") (pinfunction "7_22") (pintype "bidirectional"))
    )
  )
)
